# interface_board.net
KiCad netlist of a schematic drawn in EAGLE
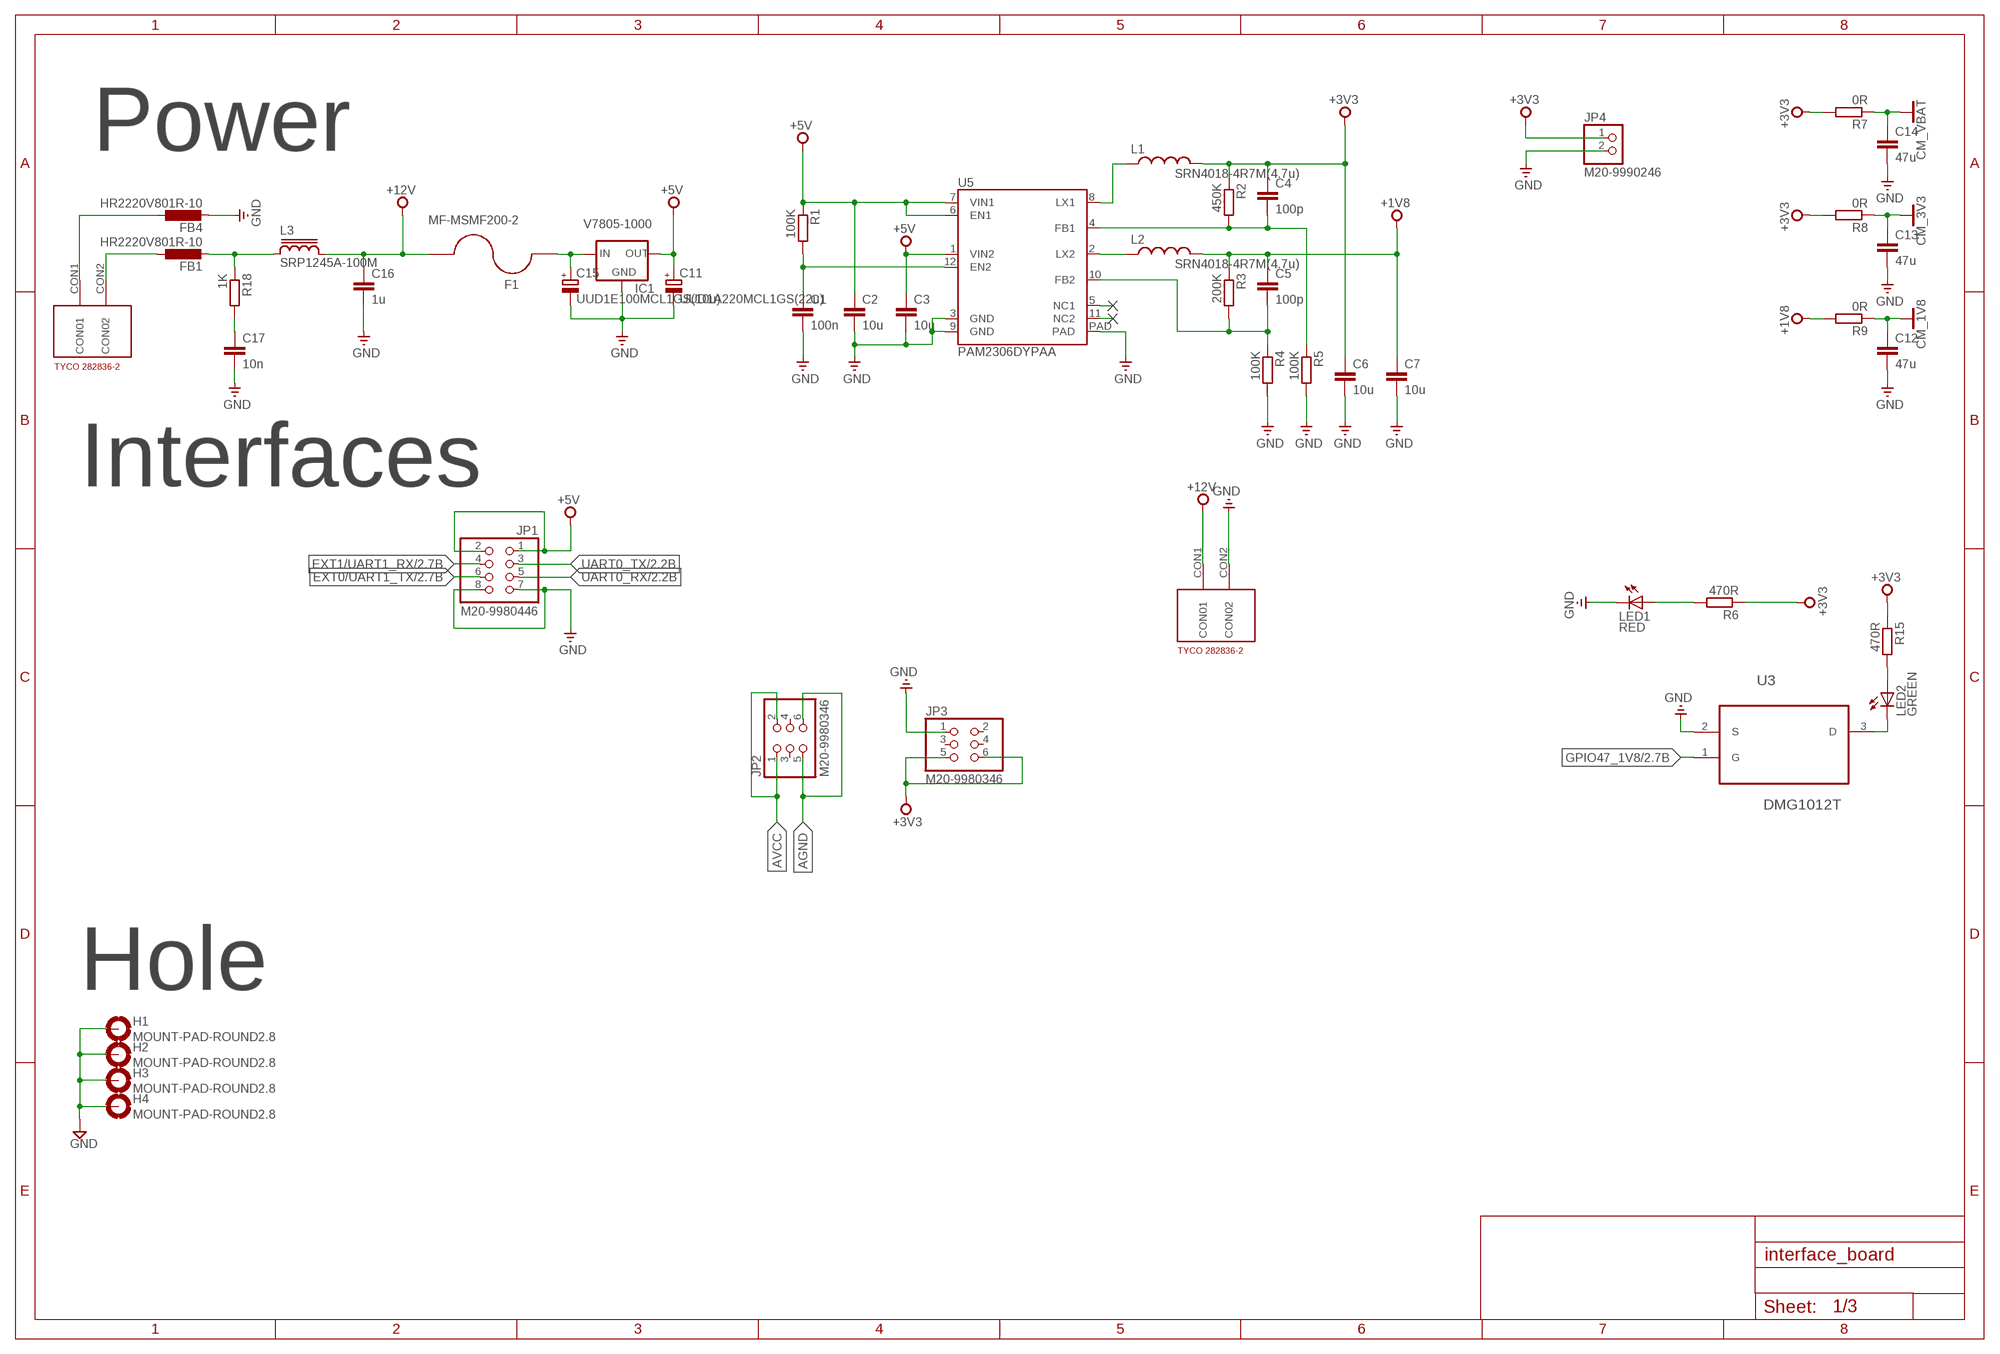
[diagram p0: schematic, sheet 1]
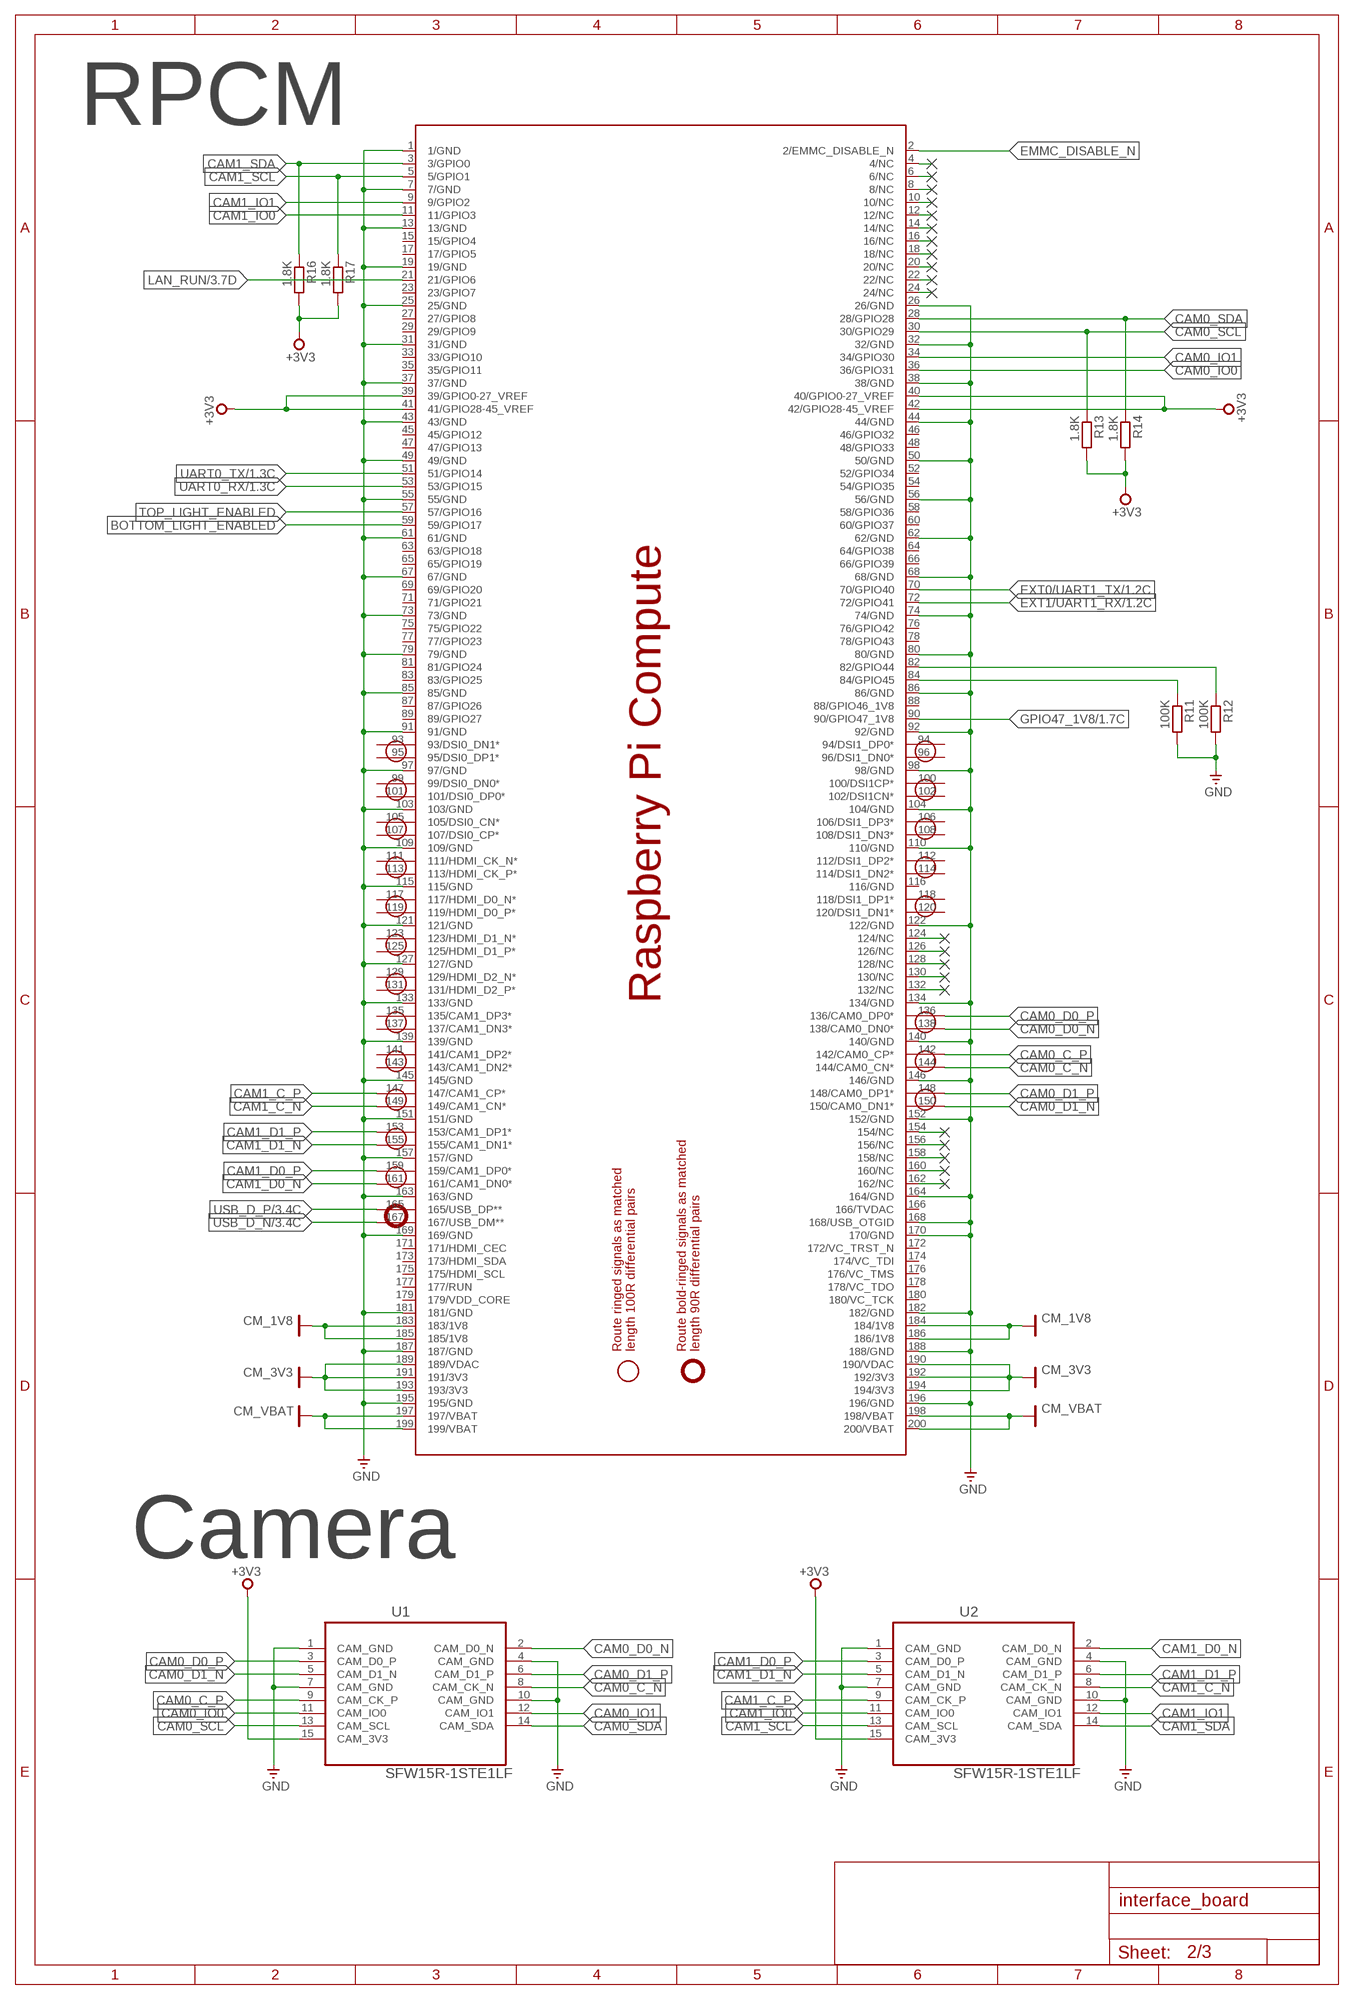
[diagram p1: schematic, sheet 2]
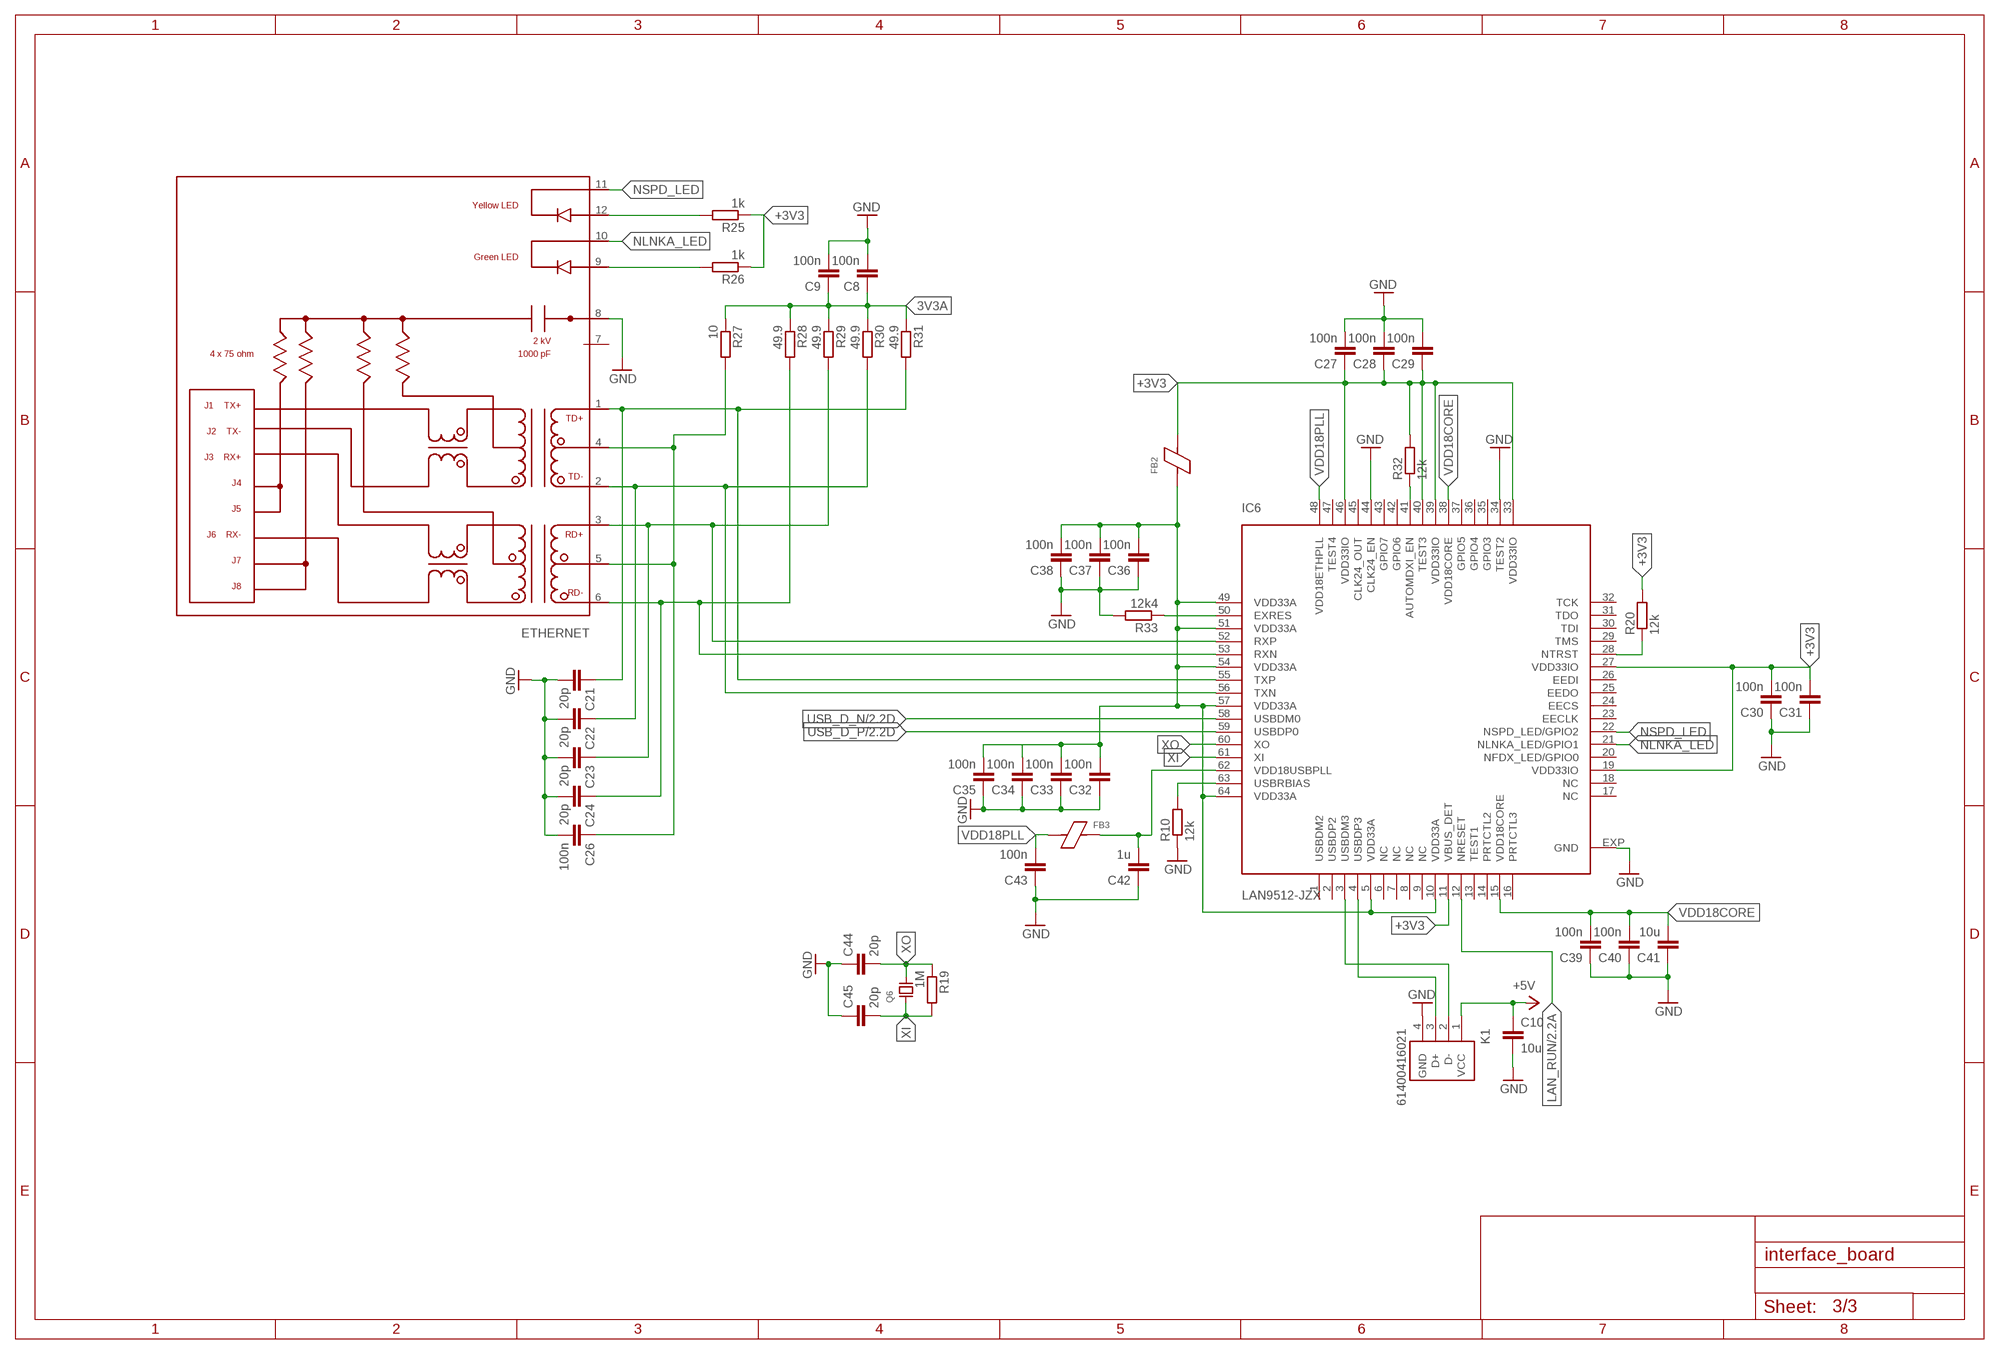
[diagram p2: schematic, sheet 3]

(export (version "E")
  (design (tool "Eeschema 10.0.6"))
  (components
    (comp (ref "C1")
      (value "100n")
      (footprint "eagle-import:C0402")
      (libsource (lib "eagle-import") (part "resistor_C-EUC0402"))
    )
    (comp (ref "C2")
      (value "10u")
      (footprint "eagle-import:C0805")
      (libsource (lib "eagle-import") (part "resistor_C-EUC0805"))
    )
    (comp (ref "C3")
      (value "10u")
      (footprint "eagle-import:C0805")
      (libsource (lib "eagle-import") (part "resistor_C-EUC0805"))
    )
    (comp (ref "C4")
      (value "100p")
      (footprint "eagle-import:C0402")
      (libsource (lib "eagle-import") (part "resistor_C-EUC0402"))
    )
    (comp (ref "C5")
      (value "100p")
      (footprint "eagle-import:C0402")
      (libsource (lib "eagle-import") (part "resistor_C-EUC0402"))
    )
    (comp (ref "C6")
      (value "10u")
      (footprint "eagle-import:C0805")
      (libsource (lib "eagle-import") (part "resistor_C-EUC0805"))
    )
    (comp (ref "C7")
      (value "10u")
      (footprint "eagle-import:C0805")
      (libsource (lib "eagle-import") (part "resistor_C-EUC0805"))
    )
    (comp (ref "C11")
      (value "UUD1A220MCL1GS(22u)")
      (footprint "eagle-import:153CLV-0405")
      (libsource (lib "eagle-import") (part "CPOL-EU153CLV-0405"))
    )
    (comp (ref "C12")
      (value "47u")
      (footprint "eagle-import:C1206")
      (libsource (lib "eagle-import") (part "resistor_C-EUC1206"))
    )
    (comp (ref "C13")
      (value "47u")
      (footprint "eagle-import:C1206")
      (libsource (lib "eagle-import") (part "resistor_C-EUC1206"))
    )
    (comp (ref "C14")
      (value "47u")
      (footprint "eagle-import:C1206")
      (libsource (lib "eagle-import") (part "resistor_C-EUC1206"))
    )
    (comp (ref "C15")
      (value "UUD1E100MCL1GS(10u)")
      (footprint "eagle-import:153CLV-0405")
      (libsource (lib "eagle-import") (part "CPOL-EU153CLV-0405"))
    )
    (comp (ref "C16")
      (value "1u")
      (footprint "eagle-import:C0402")
      (libsource (lib "eagle-import") (part "resistor_C-EUC0402"))
    )
    (comp (ref "C17")
      (value "10n")
      (footprint "eagle-import:C0402")
      (libsource (lib "eagle-import") (part "resistor_C-EUC0402"))
    )
    (comp (ref "F1")
      (value "MF-MSMF200-2")
      (footprint "eagle-import:1812")
      (fields (field (name "MANUFACTURER") "Bourns Inc.") (field (name "PART_NUMBER") "MF-MSMF075/24-2"))
      (libsource (lib "eagle-import") (part "MF-MSMF?075/24"))
    )
    (comp (ref "FB1")
      (value "HR2220V801R-10")
      (footprint "eagle-import:L5650M")
      (libsource (lib "eagle-import") (part "L-EUL5650M"))
    )
    (comp (ref "FB4")
      (value "HR2220V801R-10")
      (footprint "eagle-import:L5650M")
      (libsource (lib "eagle-import") (part "L-EUL5650M"))
    )
    (comp (ref "H1")
      (value "MOUNT-PAD-ROUND2.8")
      (footprint "eagle-import:2,8-PAD")
      (libsource (lib "eagle-import") (part "MOUNT-PAD-ROUND2.8"))
    )
    (comp (ref "H2")
      (value "MOUNT-PAD-ROUND2.8")
      (footprint "eagle-import:2,8-PAD")
      (libsource (lib "eagle-import") (part "MOUNT-PAD-ROUND2.8"))
    )
    (comp (ref "H3")
      (value "MOUNT-PAD-ROUND2.8")
      (footprint "eagle-import:2,8-PAD")
      (libsource (lib "eagle-import") (part "MOUNT-PAD-ROUND2.8"))
    )
    (comp (ref "H4")
      (value "MOUNT-PAD-ROUND2.8")
      (footprint "eagle-import:2,8-PAD")
      (libsource (lib "eagle-import") (part "MOUNT-PAD-ROUND2.8"))
    )
    (comp (ref "IC1")
      (value "V7805-1000")
      (footprint "eagle-import:DIP_3PIN")
      (libsource (lib "eagle-import") (part "VR_1OUTXX"))
    )
    (comp (ref "JP1")
      (value "M20-9980446")
      (footprint "eagle-import:2X04")
      (libsource (lib "eagle-import") (part "PINHD-2X4"))
    )
    (comp (ref "JP2")
      (value "M20-9980346")
      (footprint "eagle-import:2X03")
      (libsource (lib "eagle-import") (part "PINHD-2X3"))
    )
    (comp (ref "JP3")
      (value "M20-9980346")
      (footprint "eagle-import:2X03")
      (libsource (lib "eagle-import") (part "PINHD-2X3"))
    )
    (comp (ref "JP4")
      (value "M20-9990246")
      (footprint "eagle-import:1X02")
      (libsource (lib "eagle-import") (part "PINHD-1X2"))
    )
    (comp (ref "L1")
      (value "SRN4018-4R7M(4.7u)")
      (footprint "eagle-import:BOURNS-SRN4018")
      (libsource (lib "eagle-import") (part "BOURNS-SRN4018"))
    )
    (comp (ref "L2")
      (value "SRN4018-4R7M(4.7u)")
      (footprint "eagle-import:BOURNS-SRN4018")
      (libsource (lib "eagle-import") (part "BOURNS-SRN4018"))
    )
    (comp (ref "L3")
      (value "SRP1245A-100M")
      (footprint "eagle-import:SRP1250A")
      (libsource (lib "eagle-import") (part "SRP1250A"))
    )
    (comp (ref "LED1")
      (value "RED")
      (footprint "eagle-import:CHIP-LED0603")
      (libsource (lib "eagle-import") (part "LEDCHIP-LED0603"))
    )
    (comp (ref "LED2")
      (value "GREEN")
      (footprint "eagle-import:CHIP-LED0603")
      (libsource (lib "eagle-import") (part "LEDCHIP-LED0603"))
    )
    (comp (ref "R1")
      (value "100K")
      (footprint "eagle-import:R0402")
      (libsource (lib "eagle-import") (part "resistor_R-EU_R0402"))
    )
    (comp (ref "R2")
      (value "450K")
      (footprint "eagle-import:R0402")
      (libsource (lib "eagle-import") (part "resistor_R-EU_R0402"))
    )
    (comp (ref "R3")
      (value "200K")
      (footprint "eagle-import:R0402")
      (libsource (lib "eagle-import") (part "resistor_R-EU_R0402"))
    )
    (comp (ref "R4")
      (value "100K")
      (footprint "eagle-import:R0402")
      (libsource (lib "eagle-import") (part "resistor_R-EU_R0402"))
    )
    (comp (ref "R5")
      (value "100K")
      (footprint "eagle-import:R0402")
      (libsource (lib "eagle-import") (part "resistor_R-EU_R0402"))
    )
    (comp (ref "R6")
      (value "470R")
      (footprint "eagle-import:R0402")
      (libsource (lib "eagle-import") (part "resistor_R-EU_R0402"))
    )
    (comp (ref "R7")
      (value "0R")
      (footprint "eagle-import:R0805")
      (libsource (lib "eagle-import") (part "resistor_R-EU_R0805"))
    )
    (comp (ref "R8")
      (value "0R")
      (footprint "eagle-import:R0805")
      (libsource (lib "eagle-import") (part "resistor_R-EU_R0805"))
    )
    (comp (ref "R9")
      (value "0R")
      (footprint "eagle-import:R0805")
      (libsource (lib "eagle-import") (part "resistor_R-EU_R0805"))
    )
    (comp (ref "R15")
      (value "470R")
      (footprint "eagle-import:R0402")
      (libsource (lib "eagle-import") (part "resistor_R-EU_R0402"))
    )
    (comp (ref "R18")
      (value "1K")
      (footprint "eagle-import:R0402")
      (libsource (lib "eagle-import") (part "resistor_R-EU_R0402"))
    )
    (comp (ref "U$1")
      (value "282836-2")
      (footprint "eagle-import:282836-2")
      (libsource (lib "eagle-import") (part "282836-2"))
    )
    (comp (ref "U$2")
      (value "M20-9980346")
      (footprint "eagle-import:282836-2")
      (libsource (lib "eagle-import") (part "282836-2"))
    )
    (comp (ref "U3")
      (value "DMG1012T")
      (footprint "eagle-import:SOT523")
      (libsource (lib "eagle-import") (part "DMG1012T"))
    )
    (comp (ref "U5")
      (value "PAM2306DYPAA")
      (footprint "eagle-import:WDFN3X3-12L")
      (libsource (lib "eagle-import") (part "PAM2306"))
    )
    (comp (ref "PCB1")
      (value "1473005-4")
      (footprint "eagle-import:RPI_COMPUTE")
      (libsource (lib "eagle-import") (part "RPI_COMPUTE"))
    )
    (comp (ref "R11")
      (value "100K")
      (footprint "eagle-import:R0402")
      (libsource (lib "eagle-import") (part "resistor_R-EU_R0402"))
    )
    (comp (ref "R12")
      (value "100K")
      (footprint "eagle-import:R0402")
      (libsource (lib "eagle-import") (part "resistor_R-EU_R0402"))
    )
    (comp (ref "R13")
      (value "1.8K")
      (footprint "eagle-import:R0402")
      (libsource (lib "eagle-import") (part "resistor_R-EU_R0402"))
    )
    (comp (ref "R14")
      (value "1.8K")
      (footprint "eagle-import:R0402")
      (libsource (lib "eagle-import") (part "resistor_R-EU_R0402"))
    )
    (comp (ref "R16")
      (value "1.8K")
      (footprint "eagle-import:R0402")
      (libsource (lib "eagle-import") (part "resistor_R-EU_R0402"))
    )
    (comp (ref "R17")
      (value "1.8K")
      (footprint "eagle-import:R0402")
      (libsource (lib "eagle-import") (part "resistor_R-EU_R0402"))
    )
    (comp (ref "U1")
      (value "SFW15R-1STE1LF")
      (footprint "eagle-import:RPI_CAMERA")
      (fields (field (name "MPN") "SFW16R-1STE1LF"))
      (libsource (lib "eagle-import") (part "RPI_CAMERA"))
    )
    (comp (ref "U2")
      (value "SFW15R-1STE1LF")
      (footprint "eagle-import:RPI_CAMERA")
      (fields (field (name "MPN") "SFW16R-1STE1LF"))
      (libsource (lib "eagle-import") (part "RPI_CAMERA"))
    )
    (comp (ref "C8")
      (value "100n")
      (footprint "eagle-import:C0603")
      (libsource (lib "eagle-import") (part "C-EUC0603"))
    )
    (comp (ref "C9")
      (value "100n")
      (footprint "eagle-import:C0603")
      (libsource (lib "eagle-import") (part "C-EUC0603"))
    )
    (comp (ref "C10")
      (value "10u")
      (footprint "eagle-import:C0805")
      (libsource (lib "eagle-import") (part "C-EUC0805"))
    )
    (comp (ref "C21")
      (value "20p")
      (footprint "eagle-import:C0603")
      (libsource (lib "eagle-import") (part "C-EUC0603"))
    )
    (comp (ref "C22")
      (value "20p")
      (footprint "eagle-import:C0603")
      (libsource (lib "eagle-import") (part "C-EUC0603"))
    )
    (comp (ref "C23")
      (value "20p")
      (footprint "eagle-import:C0603")
      (libsource (lib "eagle-import") (part "C-EUC0603"))
    )
    (comp (ref "C24")
      (value "20p")
      (footprint "eagle-import:C0603")
      (libsource (lib "eagle-import") (part "C-EUC0603"))
    )
    (comp (ref "C26")
      (value "100n")
      (footprint "eagle-import:C0603")
      (libsource (lib "eagle-import") (part "C-EUC0603"))
    )
    (comp (ref "C27")
      (value "100n")
      (footprint "eagle-import:C0603")
      (libsource (lib "eagle-import") (part "C-EUC0603"))
    )
    (comp (ref "C28")
      (value "100n")
      (footprint "eagle-import:C0603")
      (libsource (lib "eagle-import") (part "C-EUC0603"))
    )
    (comp (ref "C29")
      (value "100n")
      (footprint "eagle-import:C0603")
      (libsource (lib "eagle-import") (part "C-EUC0603"))
    )
    (comp (ref "C30")
      (value "100n")
      (footprint "eagle-import:C0603")
      (libsource (lib "eagle-import") (part "C-EUC0603"))
    )
    (comp (ref "C31")
      (value "100n")
      (footprint "eagle-import:C0603")
      (libsource (lib "eagle-import") (part "C-EUC0603"))
    )
    (comp (ref "C32")
      (value "100n")
      (footprint "eagle-import:C0603")
      (libsource (lib "eagle-import") (part "C-EUC0603"))
    )
    (comp (ref "C33")
      (value "100n")
      (footprint "eagle-import:C0603")
      (libsource (lib "eagle-import") (part "C-EUC0603"))
    )
    (comp (ref "C34")
      (value "100n")
      (footprint "eagle-import:C0603")
      (libsource (lib "eagle-import") (part "C-EUC0603"))
    )
    (comp (ref "C35")
      (value "100n")
      (footprint "eagle-import:C0603")
      (libsource (lib "eagle-import") (part "C-EUC0603"))
    )
    (comp (ref "C36")
      (value "100n")
      (footprint "eagle-import:C0603")
      (libsource (lib "eagle-import") (part "C-EUC0603"))
    )
    (comp (ref "C37")
      (value "100n")
      (footprint "eagle-import:C0603")
      (libsource (lib "eagle-import") (part "C-EUC0603"))
    )
    (comp (ref "C38")
      (value "100n")
      (footprint "eagle-import:C0603")
      (libsource (lib "eagle-import") (part "C-EUC0603"))
    )
    (comp (ref "C39")
      (value "100n")
      (footprint "eagle-import:C0603")
      (libsource (lib "eagle-import") (part "C-EUC0603"))
    )
    (comp (ref "C40")
      (value "100n")
      (footprint "eagle-import:C0603")
      (libsource (lib "eagle-import") (part "C-EUC0603"))
    )
    (comp (ref "C41")
      (value "10u")
      (footprint "eagle-import:C0805")
      (libsource (lib "eagle-import") (part "C-EUC0805"))
    )
    (comp (ref "C42")
      (value "1u")
      (footprint "eagle-import:C0805")
      (libsource (lib "eagle-import") (part "C-EUC0805"))
    )
    (comp (ref "C43")
      (value "100n")
      (footprint "eagle-import:C0603")
      (libsource (lib "eagle-import") (part "C-EUC0603"))
    )
    (comp (ref "C44")
      (value "20p")
      (footprint "eagle-import:C0603")
      (libsource (lib "eagle-import") (part "C-EUC0603"))
    )
    (comp (ref "C45")
      (value "20p")
      (footprint "eagle-import:C0603")
      (libsource (lib "eagle-import") (part "C-EUC0603"))
    )
    (comp (ref "ETHERNET")
      (value "HR911105A")
      (footprint "eagle-import:RJ45")
      (libsource (lib "eagle-import") (part "HR911105A"))
    )
    (comp (ref "FB2")
      (value "742792022")
      (footprint "eagle-import:C0805")
      (libsource (lib "eagle-import") (part "FERRITE_BEAD"))
    )
    (comp (ref "FB3")
      (value "742792022")
      (footprint "eagle-import:C0805")
      (libsource (lib "eagle-import") (part "FERRITE_BEAD"))
    )
    (comp (ref "IC6")
      (value "LAN9512-JZX")
      (footprint "eagle-import:QFN64-9X9")
      (libsource (lib "eagle-import") (part "LAN9512"))
    )
    (comp (ref "K1")
      (value "61400416021")
      (footprint "eagle-import:61400416021")
      (libsource (lib "eagle-import") (part "61400416021"))
    )
    (comp (ref "Q6")
      (value "CTS_32X25_SMD")
      (footprint "eagle-import:CTS_32X25")
      (libsource (lib "eagle-import") (part "CTS_32X25_SMD"))
    )
    (comp (ref "R10")
      (value "12k")
      (footprint "eagle-import:R0603")
      (libsource (lib "eagle-import") (part "R-EU_R0603"))
    )
    (comp (ref "R19")
      (value "1M")
      (footprint "eagle-import:R0603")
      (libsource (lib "eagle-import") (part "R-EU_R0603"))
    )
    (comp (ref "R20")
      (value "12k")
      (footprint "eagle-import:R0603")
      (libsource (lib "eagle-import") (part "R-EU_R0603"))
    )
    (comp (ref "R25")
      (value "1k")
      (footprint "eagle-import:R0603")
      (libsource (lib "eagle-import") (part "R-EU_R0603"))
    )
    (comp (ref "R26")
      (value "1k")
      (footprint "eagle-import:R0603")
      (libsource (lib "eagle-import") (part "R-EU_R0603"))
    )
    (comp (ref "R27")
      (value "10")
      (footprint "eagle-import:R0603")
      (libsource (lib "eagle-import") (part "R-EU_R0603"))
    )
    (comp (ref "R28")
      (value "49.9")
      (footprint "eagle-import:R0603")
      (libsource (lib "eagle-import") (part "R-EU_R0603"))
    )
    (comp (ref "R29")
      (value "49.9")
      (footprint "eagle-import:R0603")
      (libsource (lib "eagle-import") (part "R-EU_R0603"))
    )
    (comp (ref "R30")
      (value "49.9")
      (footprint "eagle-import:R0603")
      (libsource (lib "eagle-import") (part "R-EU_R0603"))
    )
    (comp (ref "R31")
      (value "49.9")
      (footprint "eagle-import:R0603")
      (libsource (lib "eagle-import") (part "R-EU_R0603"))
    )
    (comp (ref "R32")
      (value "12k")
      (footprint "eagle-import:R0603")
      (libsource (lib "eagle-import") (part "R-EU_R0603"))
    )
    (comp (ref "R33")
      (value "12k4")
      (footprint "eagle-import:R0603")
      (libsource (lib "eagle-import") (part "R-EU_R0603"))
    )
  )
  (nets
    (net (code "1") (name "+1V8") (class "Default")
      (node (ref "C5") (pin "1") (pinfunction "1_1") (pintype "passive"))
      (node (ref "C7") (pin "1") (pinfunction "1_1") (pintype "passive"))
      (node (ref "L2") (pin "P$1") (pinfunction "1_P$1") (pintype "passive"))
      (node (ref "R3") (pin "1") (pinfunction "1_1") (pintype "passive"))
      (node (ref "R9") (pin "2") (pinfunction "2_2") (pintype "passive"))
    )
    (net (code "2") (name "+3V3") (class "Default")
      (node (ref "C27") (pin "1") (pinfunction "1_1") (pintype "passive"))
      (node (ref "C28") (pin "1") (pinfunction "1_1") (pintype "passive"))
      (node (ref "C29") (pin "1") (pinfunction "1_1") (pintype "passive"))
      (node (ref "C30") (pin "2") (pinfunction "2_2") (pintype "passive"))
      (node (ref "C31") (pin "2") (pinfunction "2_2") (pintype "passive"))
      (node (ref "C4") (pin "1") (pinfunction "1_1") (pintype "passive"))
      (node (ref "C6") (pin "1") (pinfunction "1_1") (pintype "passive"))
      (node (ref "FB2") (pin "2") (pinfunction "P$2_2") (pintype "bidirectional"))
      (node (ref "IC6") (pin "11") (pinfunction "VBUS_DET_11") (pintype "bidirectional"))
      (node (ref "IC6") (pin "19") (pinfunction "VDD33IO_19") (pintype "bidirectional"))
      (node (ref "IC6") (pin "27") (pinfunction "VDD33IO_27") (pintype "bidirectional"))
      (node (ref "IC6") (pin "33") (pinfunction "VDD33IO_33") (pintype "bidirectional"))
      (node (ref "IC6") (pin "39") (pinfunction "VDD33IO_39") (pintype "bidirectional"))
      (node (ref "IC6") (pin "40") (pinfunction "TEST3_40") (pintype "bidirectional"))
      (node (ref "IC6") (pin "46") (pinfunction "VDD33IO_46") (pintype "bidirectional"))
      (node (ref "JP3") (pin "5") (pinfunction "5_5") (pintype "passive"))
      (node (ref "JP3") (pin "6") (pinfunction "6_6") (pintype "passive"))
      (node (ref "JP4") (pin "1") (pinfunction "1_1") (pintype "passive"))
      (node (ref "L1") (pin "P$1") (pinfunction "1_P$1") (pintype "passive"))
      (node (ref "PCB1") (pin "39") (pinfunction "39/GPIO0-27_VREF_39") (pintype "bidirectional"))
      (node (ref "PCB1") (pin "40") (pinfunction "40/GPIO0-27_VREF_40") (pintype "bidirectional"))
      (node (ref "PCB1") (pin "41") (pinfunction "41/GPIO28-45_VREF_41") (pintype "bidirectional"))
      (node (ref "PCB1") (pin "42") (pinfunction "42/GPIO28-45_VREF_42") (pintype "bidirectional"))
      (node (ref "R13") (pin "2") (pinfunction "2_2") (pintype "passive"))
      (node (ref "R14") (pin "2") (pinfunction "2_2") (pintype "passive"))
      (node (ref "R15") (pin "1") (pinfunction "1_1") (pintype "passive"))
      (node (ref "R16") (pin "2") (pinfunction "2_2") (pintype "passive"))
      (node (ref "R17") (pin "2") (pinfunction "2_2") (pintype "passive"))
      (node (ref "R2") (pin "1") (pinfunction "1_1") (pintype "passive"))
      (node (ref "R20") (pin "2") (pinfunction "2_2") (pintype "passive"))
      (node (ref "R25") (pin "1") (pinfunction "1_1") (pintype "passive"))
      (node (ref "R26") (pin "1") (pinfunction "1_1") (pintype "passive"))
      (node (ref "R32") (pin "2") (pinfunction "2_2") (pintype "passive"))
      (node (ref "R6") (pin "1") (pinfunction "1_1") (pintype "passive"))
      (node (ref "R7") (pin "2") (pinfunction "2_2") (pintype "passive"))
      (node (ref "R8") (pin "2") (pinfunction "2_2") (pintype "passive"))
      (node (ref "U1") (pin "15") (pinfunction "CAM_3V3_15") (pintype "passive"))
      (node (ref "U2") (pin "15") (pinfunction "CAM_3V3_15") (pintype "passive"))
    )
    (net (code "3") (name "+5V") (class "Default")
      (node (ref "C10") (pin "1") (pinfunction "1_1") (pintype "passive"))
      (node (ref "C11") (pin "+") (pinfunction "+_+") (pintype "passive"))
      (node (ref "C2") (pin "1") (pinfunction "1_1") (pintype "passive"))
      (node (ref "C3") (pin "1") (pinfunction "1_1") (pintype "passive"))
      (node (ref "IC1") (pin "OUT") (pinfunction "OUT_OUT") (pintype "passive"))
      (node (ref "JP1") (pin "1") (pinfunction "1_1") (pintype "passive"))
      (node (ref "JP1") (pin "2") (pinfunction "2_2") (pintype "passive"))
      (node (ref "K1") (pin "1") (pinfunction "VCC_1") (pintype "passive"))
      (node (ref "R1") (pin "1") (pinfunction "1_1") (pintype "passive"))
      (node (ref "U5") (pin "1") (pinfunction "VIN2_1") (pintype "bidirectional"))
      (node (ref "U5") (pin "6") (pinfunction "EN1_6") (pintype "bidirectional"))
      (node (ref "U5") (pin "7") (pinfunction "VIN1_7") (pintype "bidirectional"))
    )
    (net (code "4") (name "+12V") (class "Default")
      (node (ref "C16") (pin "1") (pinfunction "1_1") (pintype "passive"))
      (node (ref "F1") (pin "1") (pinfunction "1_1") (pintype "passive"))
      (node (ref "L3") (pin "2") (pinfunction "2_2") (pintype "passive"))
      (node (ref "U$2") (pin "CON1") (pinfunction "CON01_CON1") (pintype "bidirectional"))
    )
    (net (code "5") (name "3V3A") (class "Default")
      (node (ref "C8") (pin "1") (pinfunction "1_1") (pintype "passive"))
      (node (ref "C9") (pin "1") (pinfunction "1_1") (pintype "passive"))
      (node (ref "R27") (pin "1") (pinfunction "1_1") (pintype "passive"))
      (node (ref "R28") (pin "1") (pinfunction "1_1") (pintype "passive"))
      (node (ref "R29") (pin "1") (pinfunction "1_1") (pintype "passive"))
      (node (ref "R30") (pin "1") (pinfunction "1_1") (pintype "passive"))
      (node (ref "R31") (pin "1") (pinfunction "1_1") (pintype "passive"))
    )
    (net (code "6") (name "AGND") (class "Default")
      (node (ref "FB4") (pin "1") (pinfunction "1_1") (pintype "passive"))
      (node (ref "JP2") (pin "5") (pinfunction "5_5") (pintype "passive"))
      (node (ref "JP2") (pin "6") (pinfunction "6_6") (pintype "passive"))
      (node (ref "U$1") (pin "CON1") (pinfunction "CON01_CON1") (pintype "bidirectional"))
    )
    (net (code "7") (name "AVCC") (class "Default")
      (node (ref "FB1") (pin "1") (pinfunction "1_1") (pintype "passive"))
      (node (ref "JP2") (pin "1") (pinfunction "1_1") (pintype "passive"))
      (node (ref "JP2") (pin "2") (pinfunction "2_2") (pintype "passive"))
      (node (ref "U$1") (pin "CON2") (pinfunction "CON02_CON2") (pintype "bidirectional"))
    )
    (net (code "8") (name "BOTTOM_LIGHT_ENABLED") (class "Default")
      (node (ref "PCB1") (pin "59") (pinfunction "59/GPIO17_59") (pintype "bidirectional"))
    )
    (net (code "9") (name "CAM0_C_N") (class "Default")
      (node (ref "PCB1") (pin "144") (pinfunction "144/CAM0_CN*_144") (pintype "bidirectional"))
      (node (ref "U1") (pin "8") (pinfunction "CAM_CK_N_8") (pintype "passive"))
    )
    (net (code "10") (name "CAM0_C_P") (class "Default")
      (node (ref "PCB1") (pin "142") (pinfunction "142/CAM0_CP*_142") (pintype "bidirectional"))
      (node (ref "U1") (pin "9") (pinfunction "CAM_CK_P_9") (pintype "passive"))
    )
    (net (code "11") (name "CAM0_D0_N") (class "Default")
      (node (ref "PCB1") (pin "138") (pinfunction "138/CAM0_DN0*_138") (pintype "bidirectional"))
      (node (ref "U1") (pin "2") (pinfunction "CAM_D0_N_2") (pintype "passive"))
    )
    (net (code "12") (name "CAM0_D0_P") (class "Default")
      (node (ref "PCB1") (pin "136") (pinfunction "136/CAM0_DP0*_136") (pintype "bidirectional"))
      (node (ref "U1") (pin "3") (pinfunction "CAM_D0_P_3") (pintype "passive"))
    )
    (net (code "13") (name "CAM0_D1_N") (class "Default")
      (node (ref "PCB1") (pin "150") (pinfunction "150/CAM0_DN1*_150") (pintype "bidirectional"))
      (node (ref "U1") (pin "5") (pinfunction "CAM_D1_N_5") (pintype "passive"))
    )
    (net (code "14") (name "CAM0_D1_P") (class "Default")
      (node (ref "PCB1") (pin "148") (pinfunction "148/CAM0_DP1*_148") (pintype "bidirectional"))
      (node (ref "U1") (pin "6") (pinfunction "CAM_D1_P_6") (pintype "passive"))
    )
    (net (code "15") (name "CAM0_IO0") (class "Default")
      (node (ref "PCB1") (pin "36") (pinfunction "36/GPIO31_36") (pintype "bidirectional"))
      (node (ref "U1") (pin "11") (pinfunction "CAM_IO0_11") (pintype "passive"))
    )
    (net (code "16") (name "CAM0_IO1") (class "Default")
      (node (ref "PCB1") (pin "34") (pinfunction "34/GPIO30_34") (pintype "bidirectional"))
      (node (ref "U1") (pin "12") (pinfunction "CAM_IO1_12") (pintype "passive"))
    )
    (net (code "17") (name "CAM0_SCL") (class "Default")
      (node (ref "PCB1") (pin "30") (pinfunction "30/GPIO29_30") (pintype "bidirectional"))
      (node (ref "R13") (pin "1") (pinfunction "1_1") (pintype "passive"))
      (node (ref "U1") (pin "13") (pinfunction "CAM_SCL_13") (pintype "passive"))
    )
    (net (code "18") (name "CAM0_SDA") (class "Default")
      (node (ref "PCB1") (pin "28") (pinfunction "28/GPIO28_28") (pintype "bidirectional"))
      (node (ref "R14") (pin "1") (pinfunction "1_1") (pintype "passive"))
      (node (ref "U1") (pin "14") (pinfunction "CAM_SDA_14") (pintype "passive"))
    )
    (net (code "19") (name "CAM1_C_N") (class "Default")
      (node (ref "PCB1") (pin "149") (pinfunction "149/CAM1_CN*_149") (pintype "bidirectional"))
      (node (ref "U2") (pin "8") (pinfunction "CAM_CK_N_8") (pintype "passive"))
    )
    (net (code "20") (name "CAM1_C_P") (class "Default")
      (node (ref "PCB1") (pin "147") (pinfunction "147/CAM1_CP*_147") (pintype "bidirectional"))
      (node (ref "U2") (pin "9") (pinfunction "CAM_CK_P_9") (pintype "passive"))
    )
    (net (code "21") (name "CAM1_D0_N") (class "Default")
      (node (ref "PCB1") (pin "161") (pinfunction "161/CAM1_DN0*_161") (pintype "bidirectional"))
      (node (ref "U2") (pin "2") (pinfunction "CAM_D0_N_2") (pintype "passive"))
    )
    (net (code "22") (name "CAM1_D0_P") (class "Default")
      (node (ref "PCB1") (pin "159") (pinfunction "159/CAM1_DP0*_159") (pintype "bidirectional"))
      (node (ref "U2") (pin "3") (pinfunction "CAM_D0_P_3") (pintype "passive"))
    )
    (net (code "23") (name "CAM1_D1_N") (class "Default")
      (node (ref "PCB1") (pin "155") (pinfunction "155/CAM1_DN1*_155") (pintype "bidirectional"))
      (node (ref "U2") (pin "5") (pinfunction "CAM_D1_N_5") (pintype "passive"))
    )
    (net (code "24") (name "CAM1_D1_P") (class "Default")
      (node (ref "PCB1") (pin "153") (pinfunction "153/CAM1_DP1*_153") (pintype "bidirectional"))
      (node (ref "U2") (pin "6") (pinfunction "CAM_D1_P_6") (pintype "passive"))
    )
    (net (code "25") (name "CAM1_IO0") (class "Default")
      (node (ref "PCB1") (pin "11") (pinfunction "11/GPIO3_11") (pintype "bidirectional"))
      (node (ref "U2") (pin "11") (pinfunction "CAM_IO0_11") (pintype "passive"))
    )
    (net (code "26") (name "CAM1_IO1") (class "Default")
      (node (ref "PCB1") (pin "9") (pinfunction "9/GPIO2_9") (pintype "bidirectional"))
      (node (ref "U2") (pin "12") (pinfunction "CAM_IO1_12") (pintype "passive"))
    )
    (net (code "27") (name "CAM1_SCL") (class "Default")
      (node (ref "PCB1") (pin "5") (pinfunction "5/GPIO1_5") (pintype "bidirectional"))
      (node (ref "R17") (pin "1") (pinfunction "1_1") (pintype "passive"))
      (node (ref "U2") (pin "13") (pinfunction "CAM_SCL_13") (pintype "passive"))
    )
    (net (code "28") (name "CAM1_SDA") (class "Default")
      (node (ref "PCB1") (pin "3") (pinfunction "3/GPIO0_3") (pintype "bidirectional"))
      (node (ref "R16") (pin "1") (pinfunction "1_1") (pintype "passive"))
      (node (ref "U2") (pin "14") (pinfunction "CAM_SDA_14") (pintype "passive"))
    )
    (net (code "29") (name "CM_1V8") (class "Default")
      (node (ref "C12") (pin "1") (pinfunction "1_1") (pintype "passive"))
      (node (ref "PCB1") (pin "183") (pinfunction "183/1V8_183") (pintype "bidirectional"))
      (node (ref "PCB1") (pin "184") (pinfunction "184/1V8_184") (pintype "bidirectional"))
      (node (ref "PCB1") (pin "185") (pinfunction "185/1V8_185") (pintype "bidirectional"))
      (node (ref "PCB1") (pin "186") (pinfunction "186/1V8_186") (pintype "bidirectional"))
      (node (ref "R9") (pin "1") (pinfunction "1_1") (pintype "passive"))
    )
    (net (code "30") (name "CM_3V3") (class "Default")
      (node (ref "C13") (pin "1") (pinfunction "1_1") (pintype "passive"))
      (node (ref "PCB1") (pin "189") (pinfunction "189/VDAC_189") (pintype "bidirectional"))
      (node (ref "PCB1") (pin "190") (pinfunction "190/VDAC_190") (pintype "bidirectional"))
      (node (ref "PCB1") (pin "191") (pinfunction "191/3V3_191") (pintype "bidirectional"))
      (node (ref "PCB1") (pin "192") (pinfunction "192/3V3_192") (pintype "bidirectional"))
      (node (ref "PCB1") (pin "193") (pinfunction "193/3V3_193") (pintype "bidirectional"))
      (node (ref "PCB1") (pin "194") (pinfunction "194/3V3_194") (pintype "bidirectional"))
      (node (ref "R8") (pin "1") (pinfunction "1_1") (pintype "passive"))
    )
    (net (code "31") (name "CM_VBAT") (class "Default")
      (node (ref "C14") (pin "1") (pinfunction "1_1") (pintype "passive"))
      (node (ref "PCB1") (pin "197") (pinfunction "197/VBAT_197") (pintype "bidirectional"))
      (node (ref "PCB1") (pin "198") (pinfunction "198/VBAT_198") (pintype "bidirectional"))
      (node (ref "PCB1") (pin "199") (pinfunction "199/VBAT_199") (pintype "bidirectional"))
      (node (ref "PCB1") (pin "200") (pinfunction "200/VBAT_200") (pintype "bidirectional"))
      (node (ref "R7") (pin "1") (pinfunction "1_1") (pintype "passive"))
    )
    (net (code "32") (name "EMMC_DISABLE_N") (class "Default")
      (node (ref "PCB1") (pin "2") (pinfunction "2/EMMC_DISABLE_N_2") (pintype "bidirectional"))
    )
    (net (code "33") (name "EXT0{slash}UART1_TX") (class "Default")
      (node (ref "JP1") (pin "6") (pinfunction "6_6") (pintype "passive"))
      (node (ref "PCB1") (pin "70") (pinfunction "70/GPIO40_70") (pintype "bidirectional"))
    )
    (net (code "34") (name "EXT1{slash}UART1_RX") (class "Default")
      (node (ref "JP1") (pin "4") (pinfunction "4_4") (pintype "passive"))
      (node (ref "PCB1") (pin "72") (pinfunction "72/GPIO41_72") (pintype "bidirectional"))
    )
    (net (code "35") (name "GND") (class "Default")
      (node (ref "C1") (pin "2") (pinfunction "2_2") (pintype "passive"))
      (node (ref "C10") (pin "2") (pinfunction "2_2") (pintype "passive"))
      (node (ref "C11") (pin "-") (pinfunction "-_-") (pintype "passive"))
      (node (ref "C12") (pin "2") (pinfunction "2_2") (pintype "passive"))
      (node (ref "C13") (pin "2") (pinfunction "2_2") (pintype "passive"))
      (node (ref "C14") (pin "2") (pinfunction "2_2") (pintype "passive"))
      (node (ref "C15") (pin "-") (pinfunction "-_-") (pintype "passive"))
      (node (ref "C16") (pin "2") (pinfunction "2_2") (pintype "passive"))
      (node (ref "C17") (pin "2") (pinfunction "2_2") (pintype "passive"))
      (node (ref "C2") (pin "2") (pinfunction "2_2") (pintype "passive"))
      (node (ref "C21") (pin "2") (pinfunction "2_2") (pintype "passive"))
      (node (ref "C22") (pin "2") (pinfunction "2_2") (pintype "passive"))
      (node (ref "C23") (pin "2") (pinfunction "2_2") (pintype "passive"))
      (node (ref "C24") (pin "2") (pinfunction "2_2") (pintype "passive"))
      (node (ref "C26") (pin "2") (pinfunction "2_2") (pintype "passive"))
      (node (ref "C27") (pin "2") (pinfunction "2_2") (pintype "passive"))
      (node (ref "C28") (pin "2") (pinfunction "2_2") (pintype "passive"))
      (node (ref "C29") (pin "2") (pinfunction "2_2") (pintype "passive"))
      (node (ref "C3") (pin "2") (pinfunction "2_2") (pintype "passive"))
      (node (ref "C30") (pin "1") (pinfunction "1_1") (pintype "passive"))
      (node (ref "C31") (pin "1") (pinfunction "1_1") (pintype "passive"))
      (node (ref "C32") (pin "1") (pinfunction "1_1") (pintype "passive"))
      (node (ref "C33") (pin "1") (pinfunction "1_1") (pintype "passive"))
      (node (ref "C34") (pin "1") (pinfunction "1_1") (pintype "passive"))
      (node (ref "C35") (pin "1") (pinfunction "1_1") (pintype "passive"))
      (node (ref "C36") (pin "1") (pinfunction "1_1") (pintype "passive"))
      (node (ref "C37") (pin "1") (pinfunction "1_1") (pintype "passive"))
      (node (ref "C38") (pin "1") (pinfunction "1_1") (pintype "passive"))
      (node (ref "C39") (pin "1") (pinfunction "1_1") (pintype "passive"))
      (node (ref "C40") (pin "1") (pinfunction "1_1") (pintype "passive"))
      (node (ref "C41") (pin "1") (pinfunction "1_1") (pintype "passive"))
      (node (ref "C42") (pin "1") (pinfunction "1_1") (pintype "passive"))
      (node (ref "C43") (pin "1") (pinfunction "1_1") (pintype "passive"))
      (node (ref "C44") (pin "1") (pinfunction "1_1") (pintype "passive"))
      (node (ref "C45") (pin "1") (pinfunction "1_1") (pintype "passive"))
      (node (ref "C6") (pin "2") (pinfunction "2_2") (pintype "passive"))
      (node (ref "C7") (pin "2") (pinfunction "2_2") (pintype "passive"))
      (node (ref "C8") (pin "2") (pinfunction "2_2") (pintype "passive"))
      (node (ref "C9") (pin "2") (pinfunction "2_2") (pintype "passive"))
      (node (ref "ETHERNET") (pin "8") (pinfunction "P$8_8") (pintype "bidirectional"))
      (node (ref "FB4") (pin "2") (pinfunction "2_2") (pintype "passive"))
      (node (ref "H1") (pin "B2,8") (pinfunction "MOUNT_B2,8") (pintype "passive"))
      (node (ref "H2") (pin "B2,8") (pinfunction "MOUNT_B2,8") (pintype "passive"))
      (node (ref "H3") (pin "B2,8") (pinfunction "MOUNT_B2,8") (pintype "passive"))
      (node (ref "H4") (pin "B2,8") (pinfunction "MOUNT_B2,8") (pintype "passive"))
      (node (ref "IC1") (pin "GND") (pinfunction "GND_GND") (pintype "input"))
      (node (ref "IC6") (pin "34") (pinfunction "TEST2_34") (pintype "bidirectional"))
      (node (ref "IC6") (pin "44") (pinfunction "CLK24_EN_44") (pintype "bidirectional"))
      (node (ref "IC6") (pin "EXP") (pinfunction "GND_EXP") (pintype "bidirectional"))
      (node (ref "JP1") (pin "7") (pinfunction "7_7") (pintype "passive"))
      (node (ref "JP1") (pin "8") (pinfunction "8_8") (pintype "passive"))
      (node (ref "JP3") (pin "1") (pinfunction "1_1") (pintype "passive"))
      (node (ref "JP4") (pin "2") (pinfunction "2_2") (pintype "passive"))
      (node (ref "K1") (pin "4") (pinfunction "GND_4") (pintype "passive"))
      (node (ref "LED1") (pin "C") (pinfunction "C_C") (pintype "passive"))
      (node (ref "PCB1") (pin "1") (pinfunction "1/GND_1") (pintype "bidirectional"))
      (node (ref "PCB1") (pin "103") (pinfunction "103/GND_103") (pintype "bidirectional"))
      (node (ref "PCB1") (pin "104") (pinfunction "104/GND_104") (pintype "bidirectional"))
      (node (ref "PCB1") (pin "109") (pinfunction "109/GND_109") (pintype "bidirectional"))
      (node (ref "PCB1") (pin "110") (pinfunction "110/GND_110") (pintype "bidirectional"))
      (node (ref "PCB1") (pin "115") (pinfunction "115/GND_115") (pintype "bidirectional"))
      (node (ref "PCB1") (pin "121") (pinfunction "121/GND_121") (pintype "bidirectional"))
      (node (ref "PCB1") (pin "122") (pinfunction "122/GND_122") (pintype "bidirectional"))
      (node (ref "PCB1") (pin "127") (pinfunction "127/GND_127") (pintype "bidirectional"))
      (node (ref "PCB1") (pin "13") (pinfunction "13/GND_13") (pintype "bidirectional"))
      (node (ref "PCB1") (pin "133") (pinfunction "133/GND_133") (pintype "bidirectional"))
      (node (ref "PCB1") (pin "134") (pinfunction "134/GND_134") (pintype "bidirectional"))
      (node (ref "PCB1") (pin "139") (pinfunction "139/GND_139") (pintype "bidirectional"))
      (node (ref "PCB1") (pin "140") (pinfunction "140/GND_140") (pintype "bidirectional"))
      (node (ref "PCB1") (pin "145") (pinfunction "145/GND_145") (pintype "bidirectional"))
      (node (ref "PCB1") (pin "146") (pinfunction "146/GND_146") (pintype "bidirectional"))
      (node (ref "PCB1") (pin "151") (pinfunction "151/GND_151") (pintype "bidirectional"))
      (node (ref "PCB1") (pin "152") (pinfunction "152/GND_152") (pintype "bidirectional"))
      (node (ref "PCB1") (pin "157") (pinfunction "157/GND_157") (pintype "bidirectional"))
      (node (ref "PCB1") (pin "163") (pinfunction "163/GND_163") (pintype "bidirectional"))
      (node (ref "PCB1") (pin "164") (pinfunction "164/GND_164") (pintype "bidirectional"))
      (node (ref "PCB1") (pin "168") (pinfunction "168/USB_OTGID_168") (pintype "bidirectional"))
      (node (ref "PCB1") (pin "169") (pinfunction "169/GND_169") (pintype "bidirectional"))
      (node (ref "PCB1") (pin "170") (pinfunction "170/GND_170") (pintype "bidirectional"))
      (node (ref "PCB1") (pin "181") (pinfunction "181/GND_181") (pintype "bidirectional"))
      (node (ref "PCB1") (pin "182") (pinfunction "182/GND_182") (pintype "bidirectional"))
      (node (ref "PCB1") (pin "187") (pinfunction "187/GND_187") (pintype "bidirectional"))
      (node (ref "PCB1") (pin "188") (pinfunction "188/GND_188") (pintype "bidirectional"))
      (node (ref "PCB1") (pin "19") (pinfunction "19/GND_19") (pintype "bidirectional"))
      (node (ref "PCB1") (pin "195") (pinfunction "195/GND_195") (pintype "bidirectional"))
      (node (ref "PCB1") (pin "196") (pinfunction "196/GND_196") (pintype "bidirectional"))
      (node (ref "PCB1") (pin "25") (pinfunction "25/GND_25") (pintype "bidirectional"))
      (node (ref "PCB1") (pin "26") (pinfunction "26/GND_26") (pintype "bidirectional"))
      (node (ref "PCB1") (pin "31") (pinfunction "31/GND_31") (pintype "bidirectional"))
      (node (ref "PCB1") (pin "32") (pinfunction "32/GND_32") (pintype "bidirectional"))
      (node (ref "PCB1") (pin "37") (pinfunction "37/GND_37") (pintype "bidirectional"))
      (node (ref "PCB1") (pin "38") (pinfunction "38/GND_38") (pintype "bidirectional"))
      (node (ref "PCB1") (pin "43") (pinfunction "43/GND_43") (pintype "bidirectional"))
      (node (ref "PCB1") (pin "44") (pinfunction "44/GND_44") (pintype "bidirectional"))
      (node (ref "PCB1") (pin "49") (pinfunction "49/GND_49") (pintype "bidirectional"))
      (node (ref "PCB1") (pin "50") (pinfunction "50/GND_50") (pintype "bidirectional"))
      (node (ref "PCB1") (pin "55") (pinfunction "55/GND_55") (pintype "bidirectional"))
      (node (ref "PCB1") (pin "56") (pinfunction "56/GND_56") (pintype "bidirectional"))
      (node (ref "PCB1") (pin "61") (pinfunction "61/GND_61") (pintype "bidirectional"))
      (node (ref "PCB1") (pin "62") (pinfunction "62/GND_62") (pintype "bidirectional"))
      (node (ref "PCB1") (pin "67") (pinfunction "67/GND_67") (pintype "bidirectional"))
      (node (ref "PCB1") (pin "68") (pinfunction "68/GND_68") (pintype "bidirectional"))
      (node (ref "PCB1") (pin "7") (pinfunction "7/GND_7") (pintype "bidirectional"))
      (node (ref "PCB1") (pin "73") (pinfunction "73/GND_73") (pintype "bidirectional"))
      (node (ref "PCB1") (pin "74") (pinfunction "74/GND_74") (pintype "bidirectional"))
      (node (ref "PCB1") (pin "79") (pinfunction "79/GND_79") (pintype "bidirectional"))
      (node (ref "PCB1") (pin "80") (pinfunction "80/GND_80") (pintype "bidirectional"))
      (node (ref "PCB1") (pin "85") (pinfunction "85/GND_85") (pintype "bidirectional"))
      (node (ref "PCB1") (pin "86") (pinfunction "86/GND_86") (pintype "bidirectional"))
      (node (ref "PCB1") (pin "91") (pinfunction "91/GND_91") (pintype "bidirectional"))
      (node (ref "PCB1") (pin "92") (pinfunction "92/GND_92") (pintype "bidirectional"))
      (node (ref "PCB1") (pin "97") (pinfunction "97/GND_97") (pintype "bidirectional"))
      (node (ref "PCB1") (pin "98") (pinfunction "98/GND_98") (pintype "bidirectional"))
      (node (ref "R10") (pin "1") (pinfunction "1_1") (pintype "passive"))
      (node (ref "R11") (pin "2") (pinfunction "2_2") (pintype "passive"))
      (node (ref "R12") (pin "2") (pinfunction "2_2") (pintype "passive"))
      (node (ref "R33") (pin "2") (pinfunction "2_2") (pintype "passive"))
      (node (ref "R4") (pin "2") (pinfunction "2_2") (pintype "passive"))
      (node (ref "R5") (pin "2") (pinfunction "2_2") (pintype "passive"))
      (node (ref "U$2") (pin "CON2") (pinfunction "CON02_CON2") (pintype "bidirectional"))
      (node (ref "U1") (pin "1") (pinfunction "CAM_GND_1") (pintype "passive"))
      (node (ref "U1") (pin "10") (pinfunction "CAM_GND_10") (pintype "passive"))
      (node (ref "U1") (pin "4") (pinfunction "CAM_GND_4") (pintype "passive"))
      (node (ref "U1") (pin "7") (pinfunction "CAM_GND_7") (pintype "passive"))
      (node (ref "U2") (pin "1") (pinfunction "CAM_GND_1") (pintype "passive"))
      (node (ref "U2") (pin "10") (pinfunction "CAM_GND_10") (pintype "passive"))
      (node (ref "U2") (pin "4") (pinfunction "CAM_GND_4") (pintype "passive"))
      (node (ref "U2") (pin "7") (pinfunction "CAM_GND_7") (pintype "passive"))
      (node (ref "U3") (pin "2") (pinfunction "S_2") (pintype "passive"))
      (node (ref "U5") (pin "3") (pinfunction "GND_3") (pintype "bidirectional"))
      (node (ref "U5") (pin "9") (pinfunction "GND_9") (pintype "bidirectional"))
      (node (ref "U5") (pin "PAD") (pinfunction "PAD_PAD") (pintype "bidirectional"))
    )
    (net (code "36") (name "GPIO47_1V8") (class "Default")
      (node (ref "PCB1") (pin "90") (pinfunction "90/GPIO47_1V8_90") (pintype "bidirectional"))
      (node (ref "U3") (pin "1") (pinfunction "G_1") (pintype "power_in"))
    )
    (net (code "37") (name "LAN_RUN") (class "Default")
      (node (ref "IC6") (pin "12") (pinfunction "NRESET_12") (pintype "bidirectional"))
      (node (ref "PCB1") (pin "21") (pinfunction "21/GPIO6_21") (pintype "bidirectional"))
    )
    (net (code "38") (name "NLNKA_LED") (class "Default")
      (node (ref "ETHERNET") (pin "10") (pinfunction "P$10_10") (pintype "bidirectional"))
      (node (ref "IC6") (pin "21") (pinfunction "NLNKA_LED/GPIO1_21") (pintype "bidirectional"))
    )
    (net (code "39") (name "NSPD_LED") (class "Default")
      (node (ref "ETHERNET") (pin "11") (pinfunction "P$11_11") (pintype "bidirectional"))
      (node (ref "IC6") (pin "22") (pinfunction "NSPD_LED/GPIO2_22") (pintype "bidirectional"))
    )
    (net (code "40") (name "Net-(C15-Pad+)") (class "Default")
      (node (ref "C15") (pin "+") (pinfunction "+_+") (pintype "passive"))
      (node (ref "F1") (pin "2") (pinfunction "2_2") (pintype "passive"))
      (node (ref "IC1") (pin "IN") (pinfunction "IN_IN") (pintype "input"))
    )
    (net (code "41") (name "Net-(C17-Pad1)") (class "Default")
      (node (ref "C17") (pin "1") (pinfunction "1_1") (pintype "passive"))
      (node (ref "R18") (pin "2") (pinfunction "2_2") (pintype "passive"))
    )
    (net (code "42") (name "Net-(ETHERNET-P$1)") (class "Default")
      (node (ref "C21") (pin "1") (pinfunction "1_1") (pintype "passive"))
      (node (ref "ETHERNET") (pin "1") (pinfunction "P$1_1") (pintype "bidirectional"))
      (node (ref "IC6") (pin "55") (pinfunction "TXP_55") (pintype "bidirectional"))
      (node (ref "R31") (pin "2") (pinfunction "2_2") (pintype "passive"))
    )
    (net (code "43") (name "Net-(ETHERNET-P$2)") (class "Default")
      (node (ref "C22") (pin "1") (pinfunction "1_1") (pintype "passive"))
      (node (ref "ETHERNET") (pin "2") (pinfunction "P$2_2") (pintype "bidirectional"))
      (node (ref "IC6") (pin "56") (pinfunction "TXN_56") (pintype "bidirectional"))
      (node (ref "R30") (pin "2") (pinfunction "2_2") (pintype "passive"))
    )
    (net (code "44") (name "Net-(ETHERNET-P$3)") (class "Default")
      (node (ref "C23") (pin "1") (pinfunction "1_1") (pintype "passive"))
      (node (ref "ETHERNET") (pin "3") (pinfunction "P$3_3") (pintype "bidirectional"))
      (node (ref "IC6") (pin "52") (pinfunction "RXP_52") (pintype "bidirectional"))
      (node (ref "R29") (pin "2") (pinfunction "2_2") (pintype "passive"))
    )
    (net (code "45") (name "Net-(ETHERNET-P$4)") (class "Default")
      (node (ref "C26") (pin "1") (pinfunction "1_1") (pintype "passive"))
      (node (ref "ETHERNET") (pin "4") (pinfunction "P$4_4") (pintype "bidirectional"))
      (node (ref "ETHERNET") (pin "5") (pinfunction "P$5_5") (pintype "bidirectional"))
      (node (ref "R27") (pin "2") (pinfunction "2_2") (pintype "passive"))
    )
    (net (code "46") (name "Net-(ETHERNET-P$6)") (class "Default")
      (node (ref "C24") (pin "1") (pinfunction "1_1") (pintype "passive"))
      (node (ref "ETHERNET") (pin "6") (pinfunction "P$6_6") (pintype "bidirectional"))
      (node (ref "IC6") (pin "53") (pinfunction "RXN_53") (pintype "bidirectional"))
      (node (ref "R28") (pin "2") (pinfunction "2_2") (pintype "passive"))
    )
    (net (code "47") (name "Net-(ETHERNET-P$9)") (class "Default")
      (node (ref "ETHERNET") (pin "9") (pinfunction "P$9_9") (pintype "bidirectional"))
      (node (ref "R26") (pin "2") (pinfunction "2_2") (pintype "passive"))
    )
    (net (code "48") (name "Net-(ETHERNET-P$12)") (class "Default")
      (node (ref "ETHERNET") (pin "12") (pinfunction "P$12_12") (pintype "bidirectional"))
      (node (ref "R25") (pin "2") (pinfunction "2_2") (pintype "passive"))
    )
    (net (code "49") (name "Net-(FB1-Pad2)") (class "Default")
      (node (ref "FB1") (pin "2") (pinfunction "2_2") (pintype "passive"))
      (node (ref "L3") (pin "1") (pinfunction "1_1") (pintype "passive"))
      (node (ref "R18") (pin "1") (pinfunction "1_1") (pintype "passive"))
    )
    (net (code "50") (name "Net-(FB2-P$1)") (class "Default")
      (node (ref "C32") (pin "2") (pinfunction "2_2") (pintype "passive"))
      (node (ref "C33") (pin "2") (pinfunction "2_2") (pintype "passive"))
      (node (ref "C34") (pin "2") (pinfunction "2_2") (pintype "passive"))
      (node (ref "C35") (pin "2") (pinfunction "2_2") (pintype "passive"))
      (node (ref "C36") (pin "2") (pinfunction "2_2") (pintype "passive"))
      (node (ref "C37") (pin "2") (pinfunction "2_2") (pintype "passive"))
      (node (ref "C38") (pin "2") (pinfunction "2_2") (pintype "passive"))
      (node (ref "FB2") (pin "1") (pinfunction "P$1_1") (pintype "bidirectional"))
      (node (ref "IC6") (pin "10") (pinfunction "VDD33A_10") (pintype "bidirectional"))
      (node (ref "IC6") (pin "49") (pinfunction "VDD33A_49") (pintype "bidirectional"))
      (node (ref "IC6") (pin "5") (pinfunction "VDD33A_5") (pintype "bidirectional"))
      (node (ref "IC6") (pin "51") (pinfunction "VDD33A_51") (pintype "bidirectional"))
      (node (ref "IC6") (pin "54") (pinfunction "VDD33A_54") (pintype "bidirectional"))
      (node (ref "IC6") (pin "57") (pinfunction "VDD33A_57") (pintype "bidirectional"))
      (node (ref "IC6") (pin "64") (pinfunction "VDD33A_64") (pintype "bidirectional"))
    )
    (net (code "51") (name "Net-(FB3-P$2)") (class "Default")
      (node (ref "C42") (pin "2") (pinfunction "2_2") (pintype "passive"))
      (node (ref "FB3") (pin "2") (pinfunction "P$2_2") (pintype "bidirectional"))
      (node (ref "IC6") (pin "62") (pinfunction "VDD18USBPLL_62") (pintype "bidirectional"))
    )
    (net (code "52") (name "Net-(IC6-AUTOMDXI_EN)") (class "Default")
      (node (ref "IC6") (pin "41") (pinfunction "AUTOMDXI_EN_41") (pintype "bidirectional"))
      (node (ref "R32") (pin "1") (pinfunction "1_1") (pintype "passive"))
    )
    (net (code "53") (name "Net-(IC6-EXRES)") (class "Default")
      (node (ref "IC6") (pin "50") (pinfunction "EXRES_50") (pintype "bidirectional"))
      (node (ref "R33") (pin "1") (pinfunction "1_1") (pintype "passive"))
    )
    (net (code "54") (name "Net-(IC6-NTRST)") (class "Default")
      (node (ref "IC6") (pin "28") (pinfunction "NTRST_28") (pintype "bidirectional"))
      (node (ref "R20") (pin "1") (pinfunction "1_1") (pintype "passive"))
    )
    (net (code "55") (name "Net-(IC6-USBDM3)") (class "Default")
      (node (ref "IC6") (pin "3") (pinfunction "USBDM3_3") (pintype "bidirectional"))
      (node (ref "K1") (pin "2") (pinfunction "D-_2") (pintype "passive"))
    )
    (net (code "56") (name "Net-(IC6-USBDP3)") (class "Default")
      (node (ref "IC6") (pin "4") (pinfunction "USBDP3_4") (pintype "bidirectional"))
      (node (ref "K1") (pin "3") (pinfunction "D+_3") (pintype "passive"))
    )
    (net (code "57") (name "Net-(IC6-USBRBIAS)") (class "Default")
      (node (ref "IC6") (pin "63") (pinfunction "USBRBIAS_63") (pintype "bidirectional"))
      (node (ref "R10") (pin "2") (pinfunction "2_2") (pintype "passive"))
    )
    (net (code "58") (name "Net-(L1-2)") (class "Default")
      (node (ref "L1") (pin "P$2") (pinfunction "2_P$2") (pintype "passive"))
      (node (ref "U5") (pin "8") (pinfunction "LX1_8") (pintype "bidirectional"))
    )
    (net (code "59") (name "Net-(L2-2)") (class "Default")
      (node (ref "L2") (pin "P$2") (pinfunction "2_P$2") (pintype "passive"))
      (node (ref "U5") (pin "2") (pinfunction "LX2_2") (pintype "bidirectional"))
    )
    (net (code "60") (name "Net-(LED1-PadA)") (class "Default")
      (node (ref "LED1") (pin "A") (pinfunction "A_A") (pintype "passive"))
      (node (ref "R6") (pin "2") (pinfunction "2_2") (pintype "passive"))
    )
    (net (code "61") (name "Net-(LED2-PadA)") (class "Default")
      (node (ref "LED2") (pin "A") (pinfunction "A_A") (pintype "passive"))
      (node (ref "R15") (pin "2") (pinfunction "2_2") (pintype "passive"))
    )
    (net (code "62") (name "Net-(PCB1-82{slash}GPIO44)") (class "Default")
      (node (ref "PCB1") (pin "82") (pinfunction "82/GPIO44_82") (pintype "bidirectional"))
      (node (ref "R12") (pin "1") (pinfunction "1_1") (pintype "passive"))
    )
    (net (code "63") (name "Net-(PCB1-84{slash}GPIO45)") (class "Default")
      (node (ref "PCB1") (pin "84") (pinfunction "84/GPIO45_84") (pintype "bidirectional"))
      (node (ref "R11") (pin "1") (pinfunction "1_1") (pintype "passive"))
    )
    (net (code "64") (name "Net-(U3-D)") (class "Default")
      (node (ref "LED2") (pin "C") (pinfunction "C_C") (pintype "passive"))
      (node (ref "U3") (pin "3") (pinfunction "D_3") (pintype "output"))
    )
    (net (code "65") (name "Net-(U5-EN2)") (class "Default")
      (node (ref "C1") (pin "1") (pinfunction "1_1") (pintype "passive"))
      (node (ref "R1") (pin "2") (pinfunction "2_2") (pintype "passive"))
      (node (ref "U5") (pin "12") (pinfunction "EN2_12") (pintype "bidirectional"))
    )
    (net (code "66") (name "Net-(U5-FB1)") (class "Default")
      (node (ref "C4") (pin "2") (pinfunction "2_2") (pintype "passive"))
      (node (ref "R2") (pin "2") (pinfunction "2_2") (pintype "passive"))
      (node (ref "R5") (pin "1") (pinfunction "1_1") (pintype "passive"))
      (node (ref "U5") (pin "4") (pinfunction "FB1_4") (pintype "bidirectional"))
    )
    (net (code "67") (name "Net-(U5-FB2)") (class "Default")
      (node (ref "C5") (pin "2") (pinfunction "2_2") (pintype "passive"))
      (node (ref "R3") (pin "2") (pinfunction "2_2") (pintype "passive"))
      (node (ref "R4") (pin "1") (pinfunction "1_1") (pintype "passive"))
      (node (ref "U5") (pin "10") (pinfunction "FB2_10") (pintype "bidirectional"))
    )
    (net (code "68") (name "TOP_LIGHT_ENABLED") (class "Default")
      (node (ref "PCB1") (pin "57") (pinfunction "57/GPIO16_57") (pintype "bidirectional"))
    )
    (net (code "69") (name "UART0_RX") (class "Default")
      (node (ref "JP1") (pin "5") (pinfunction "5_5") (pintype "passive"))
      (node (ref "PCB1") (pin "53") (pinfunction "53/GPIO15_53") (pintype "bidirectional"))
    )
    (net (code "70") (name "UART0_TX") (class "Default")
      (node (ref "JP1") (pin "3") (pinfunction "3_3") (pintype "passive"))
      (node (ref "PCB1") (pin "51") (pinfunction "51/GPIO14_51") (pintype "bidirectional"))
    )
    (net (code "71") (name "USB_D_N") (class "Default")
      (node (ref "IC6") (pin "58") (pinfunction "USBDM0_58") (pintype "bidirectional"))
      (node (ref "PCB1") (pin "167") (pinfunction "167/USB_DM**_167") (pintype "bidirectional"))
    )
    (net (code "72") (name "USB_D_P") (class "Default")
      (node (ref "IC6") (pin "59") (pinfunction "USBDP0_59") (pintype "bidirectional"))
      (node (ref "PCB1") (pin "165") (pinfunction "165/USB_DP**_165") (pintype "bidirectional"))
    )
    (net (code "73") (name "VDD18CORE") (class "Default")
      (node (ref "C39") (pin "2") (pinfunction "2_2") (pintype "passive"))
      (node (ref "C40") (pin "2") (pinfunction "2_2") (pintype "passive"))
      (node (ref "C41") (pin "2") (pinfunction "2_2") (pintype "passive"))
      (node (ref "IC6") (pin "15") (pinfunction "VDD18CORE_15") (pintype "bidirectional"))
      (node (ref "IC6") (pin "38") (pinfunction "VDD18CORE_38") (pintype "bidirectional"))
    )
    (net (code "74") (name "VDD18PLL") (class "Default")
      (node (ref "C43") (pin "2") (pinfunction "2_2") (pintype "passive"))
      (node (ref "FB3") (pin "1") (pinfunction "P$1_1") (pintype "bidirectional"))
      (node (ref "IC6") (pin "48") (pinfunction "VDD18ETHPLL_48") (pintype "bidirectional"))
    )
    (net (code "75") (name "XI") (class "Default")
      (node (ref "C45") (pin "2") (pinfunction "2_2") (pintype "passive"))
      (node (ref "IC6") (pin "61") (pinfunction "XI_61") (pintype "bidirectional"))
      (node (ref "Q6") (pin "1") (pinfunction "X1_1") (pintype "bidirectional"))
      (node (ref "R19") (pin "2") (pinfunction "2_2") (pintype "passive"))
    )
    (net (code "76") (name "XO") (class "Default")
      (node (ref "C44") (pin "2") (pinfunction "2_2") (pintype "passive"))
      (node (ref "IC6") (pin "60") (pinfunction "XO_60") (pintype "bidirectional"))
      (node (ref "Q6") (pin "3") (pinfunction "X2_3") (pintype "bidirectional"))
      (node (ref "R19") (pin "1") (pinfunction "1_1") (pintype "passive"))
    )
    (net (code "77") (name "unconnected-(ETHERNET-P$7-Pad7)") (class "Default")
      (node (ref "ETHERNET") (pin "7") (pinfunction "P$7_7") (pintype "bidirectional"))
    )
    (net (code "78") (name "unconnected-(IC6-CLK24_OUT-Pad45)") (class "Default")
      (node (ref "IC6") (pin "45") (pinfunction "CLK24_OUT_45") (pintype "bidirectional"))
    )
    (net (code "79") (name "unconnected-(IC6-EECLK-Pad23)") (class "Default")
      (node (ref "IC6") (pin "23") (pinfunction "EECLK_23") (pintype "bidirectional"))
    )
    (net (code "80") (name "unconnected-(IC6-EECS-Pad24)") (class "Default")
      (node (ref "IC6") (pin "24") (pinfunction "EECS_24") (pintype "bidirectional"))
    )
    (net (code "81") (name "unconnected-(IC6-EEDI-Pad26)") (class "Default")
      (node (ref "IC6") (pin "26") (pinfunction "EEDI_26") (pintype "bidirectional"))
    )
    (net (code "82") (name "unconnected-(IC6-EEDO-Pad25)") (class "Default")
      (node (ref "IC6") (pin "25") (pinfunction "EEDO_25") (pintype "bidirectional"))
    )
    (net (code "83") (name "unconnected-(IC6-GPIO3-Pad35)") (class "Default")
      (node (ref "IC6") (pin "35") (pinfunction "GPIO3_35") (pintype "bidirectional"))
    )
    (net (code "84") (name "unconnected-(IC6-GPIO4-Pad36)") (class "Default")
      (node (ref "IC6") (pin "36") (pinfunction "GPIO4_36") (pintype "bidirectional"))
    )
    (net (code "85") (name "unconnected-(IC6-GPIO5-Pad37)") (class "Default")
      (node (ref "IC6") (pin "37") (pinfunction "GPIO5_37") (pintype "bidirectional"))
    )
    (net (code "86") (name "unconnected-(IC6-GPIO6-Pad42)") (class "Default")
      (node (ref "IC6") (pin "42") (pinfunction "GPIO6_42") (pintype "bidirectional"))
    )
    (net (code "87") (name "unconnected-(IC6-GPIO7-Pad43)") (class "Default")
      (node (ref "IC6") (pin "43") (pinfunction "GPIO7_43") (pintype "bidirectional"))
    )
    (net (code "88") (name "unconnected-(IC6-NC-Pad6)") (class "Default")
      (node (ref "IC6") (pin "6") (pinfunction "NC_6") (pintype "bidirectional"))
    )
    (net (code "89") (name "unconnected-(IC6-NC-Pad7)") (class "Default")
      (node (ref "IC6") (pin "7") (pinfunction "NC_7") (pintype "bidirectional"))
    )
    (net (code "90") (name "unconnected-(IC6-NC-Pad8)") (class "Default")
      (node (ref "IC6") (pin "8") (pinfunction "NC_8") (pintype "bidirectional"))
    )
    (net (code "91") (name "unconnected-(IC6-NC-Pad9)") (class "Default")
      (node (ref "IC6") (pin "9") (pinfunction "NC_9") (pintype "bidirectional"))
    )
    (net (code "92") (name "unconnected-(IC6-NC-Pad17)") (class "Default")
      (node (ref "IC6") (pin "17") (pinfunction "NC_17") (pintype "bidirectional"))
    )
    (net (code "93") (name "unconnected-(IC6-NC-Pad18)") (class "Default")
      (node (ref "IC6") (pin "18") (pinfunction "NC_18") (pintype "bidirectional"))
    )
    (net (code "94") (name "unconnected-(IC6-NFDX_LED{slash}GPIO0-Pad20)") (class "Default")
      (node (ref "IC6") (pin "20") (pinfunction "NFDX_LED/GPIO0_20") (pintype "bidirectional"))
    )
    (net (code "95") (name "unconnected-(IC6-PRTCTL2-Pad14)") (class "Default")
      (node (ref "IC6") (pin "14") (pinfunction "PRTCTL2_14") (pintype "bidirectional"))
    )
    (net (code "96") (name "unconnected-(IC6-PRTCTL3-Pad16)") (class "Default")
      (node (ref "IC6") (pin "16") (pinfunction "PRTCTL3_16") (pintype "bidirectional"))
    )
    (net (code "97") (name "unconnected-(IC6-TCK-Pad32)") (class "Default")
      (node (ref "IC6") (pin "32") (pinfunction "TCK_32") (pintype "bidirectional"))
    )
    (net (code "98") (name "unconnected-(IC6-TDI-Pad30)") (class "Default")
      (node (ref "IC6") (pin "30") (pinfunction "TDI_30") (pintype "bidirectional"))
    )
    (net (code "99") (name "unconnected-(IC6-TDO-Pad31)") (class "Default")
      (node (ref "IC6") (pin "31") (pinfunction "TDO_31") (pintype "bidirectional"))
    )
    (net (code "100") (name "unconnected-(IC6-TEST1-Pad13)") (class "Default")
      (node (ref "IC6") (pin "13") (pinfunction "TEST1_13") (pintype "bidirectional"))
    )
    (net (code "101") (name "unconnected-(IC6-TEST4-Pad47)") (class "Default")
      (node (ref "IC6") (pin "47") (pinfunction "TEST4_47") (pintype "bidirectional"))
    )
    (net (code "102") (name "unconnected-(IC6-TMS-Pad29)") (class "Default")
      (node (ref "IC6") (pin "29") (pinfunction "TMS_29") (pintype "bidirectional"))
    )
    (net (code "103") (name "unconnected-(IC6-USBDM2-Pad1)") (class "Default")
      (node (ref "IC6") (pin "1") (pinfunction "USBDM2_1") (pintype "bidirectional"))
    )
    (net (code "104") (name "unconnected-(IC6-USBDP2-Pad2)") (class "Default")
      (node (ref "IC6") (pin "2") (pinfunction "USBDP2_2") (pintype "bidirectional"))
    )
    (net (code "105") (name "unconnected-(JP2-Pad3)") (class "Default")
      (node (ref "JP2") (pin "3") (pinfunction "3_3") (pintype "passive"))
    )
    (net (code "106") (name "unconnected-(JP2-Pad4)") (class "Default")
      (node (ref "JP2") (pin "4") (pinfunction "4_4") (pintype "passive"))
    )
    (net (code "107") (name "unconnected-(JP3-Pad2)") (class "Default")
      (node (ref "JP3") (pin "2") (pinfunction "2_2") (pintype "passive"))
    )
    (net (code "108") (name "unconnected-(JP3-Pad3)") (class "Default")
      (node (ref "JP3") (pin "3") (pinfunction "3_3") (pintype "passive"))
    )
    (net (code "109") (name "unconnected-(JP3-Pad4)") (class "Default")
      (node (ref "JP3") (pin "4") (pinfunction "4_4") (pintype "passive"))
    )
    (net (code "110") (name "unconnected-(PCB1-4{slash}NC-Pad4)") (class "Default")
      (node (ref "PCB1") (pin "4") (pinfunction "4/NC_4") (pintype "bidirectional"))
    )
    (net (code "111") (name "unconnected-(PCB1-6{slash}NC-Pad6)") (class "Default")
      (node (ref "PCB1") (pin "6") (pinfunction "6/NC_6") (pintype "bidirectional"))
    )
    (net (code "112") (name "unconnected-(PCB1-8{slash}NC-Pad8)") (class "Default")
      (node (ref "PCB1") (pin "8") (pinfunction "8/NC_8") (pintype "bidirectional"))
    )
    (net (code "113") (name "unconnected-(PCB1-10{slash}NC-Pad10)") (class "Default")
      (node (ref "PCB1") (pin "10") (pinfunction "10/NC_10") (pintype "bidirectional"))
    )
    (net (code "114") (name "unconnected-(PCB1-12{slash}NC-Pad12)") (class "Default")
      (node (ref "PCB1") (pin "12") (pinfunction "12/NC_12") (pintype "bidirectional"))
    )
    (net (code "115") (name "unconnected-(PCB1-14{slash}NC-Pad14)") (class "Default")
      (node (ref "PCB1") (pin "14") (pinfunction "14/NC_14") (pintype "bidirectional"))
    )
    (net (code "116") (name "unconnected-(PCB1-15{slash}GPIO4-Pad15)") (class "Default")
      (node (ref "PCB1") (pin "15") (pinfunction "15/GPIO4_15") (pintype "bidirectional"))
    )
    (net (code "117") (name "unconnected-(PCB1-16{slash}NC-Pad16)") (class "Default")
      (node (ref "PCB1") (pin "16") (pinfunction "16/NC_16") (pintype "bidirectional"))
    )
    (net (code "118") (name "unconnected-(PCB1-17{slash}GPIO5-Pad17)") (class "Default")
      (node (ref "PCB1") (pin "17") (pinfunction "17/GPIO5_17") (pintype "bidirectional"))
    )
    (net (code "119") (name "unconnected-(PCB1-18{slash}NC-Pad18)") (class "Default")
      (node (ref "PCB1") (pin "18") (pinfunction "18/NC_18") (pintype "bidirectional"))
    )
    (net (code "120") (name "unconnected-(PCB1-20{slash}NC-Pad20)") (class "Default")
      (node (ref "PCB1") (pin "20") (pinfunction "20/NC_20") (pintype "bidirectional"))
    )
    (net (code "121") (name "unconnected-(PCB1-22{slash}NC-Pad22)") (class "Default")
      (node (ref "PCB1") (pin "22") (pinfunction "22/NC_22") (pintype "bidirectional"))
    )
    (net (code "122") (name "unconnected-(PCB1-23{slash}GPIO7-Pad23)") (class "Default")
      (node (ref "PCB1") (pin "23") (pinfunction "23/GPIO7_23") (pintype "bidirectional"))
    )
    (net (code "123") (name "unconnected-(PCB1-24{slash}NC-Pad24)") (class "Default")
      (node (ref "PCB1") (pin "24") (pinfunction "24/NC_24") (pintype "bidirectional"))
    )
    (net (code "124") (name "unconnected-(PCB1-27{slash}GPIO8-Pad27)") (class "Default")
      (node (ref "PCB1") (pin "27") (pinfunction "27/GPIO8_27") (pintype "bidirectional"))
    )
    (net (code "125") (name "unconnected-(PCB1-29{slash}GPIO9-Pad29)") (class "Default")
      (node (ref "PCB1") (pin "29") (pinfunction "29/GPIO9_29") (pintype "bidirectional"))
    )
    (net (code "126") (name "unconnected-(PCB1-33{slash}GPIO10-Pad33)") (class "Default")
      (node (ref "PCB1") (pin "33") (pinfunction "33/GPIO10_33") (pintype "bidirectional"))
    )
    (net (code "127") (name "unconnected-(PCB1-35{slash}GPIO11-Pad35)") (class "Default")
      (node (ref "PCB1") (pin "35") (pinfunction "35/GPIO11_35") (pintype "bidirectional"))
    )
    (net (code "128") (name "unconnected-(PCB1-45{slash}GPIO12-Pad45)") (class "Default")
      (node (ref "PCB1") (pin "45") (pinfunction "45/GPIO12_45") (pintype "bidirectional"))
    )
    (net (code "129") (name "unconnected-(PCB1-46{slash}GPIO32-Pad46)") (class "Default")
      (node (ref "PCB1") (pin "46") (pinfunction "46/GPIO32_46") (pintype "bidirectional"))
    )
    (net (code "130") (name "unconnected-(PCB1-47{slash}GPIO13-Pad47)") (class "Default")
      (node (ref "PCB1") (pin "47") (pinfunction "47/GPIO13_47") (pintype "bidirectional"))
    )
    (net (code "131") (name "unconnected-(PCB1-48{slash}GPIO33-Pad48)") (class "Default")
      (node (ref "PCB1") (pin "48") (pinfunction "48/GPIO33_48") (pintype "bidirectional"))
    )
    (net (code "132") (name "unconnected-(PCB1-52{slash}GPIO34-Pad52)") (class "Default")
      (node (ref "PCB1") (pin "52") (pinfunction "52/GPIO34_52") (pintype "bidirectional"))
    )
    (net (code "133") (name "unconnected-(PCB1-54{slash}GPIO35-Pad54)") (class "Default")
      (node (ref "PCB1") (pin "54") (pinfunction "54/GPIO35_54") (pintype "bidirectional"))
    )
    (net (code "134") (name "unconnected-(PCB1-58{slash}GPIO36-Pad58)") (class "Default")
      (node (ref "PCB1") (pin "58") (pinfunction "58/GPIO36_58") (pintype "bidirectional"))
    )
    (net (code "135") (name "unconnected-(PCB1-60{slash}GPIO37-Pad60)") (class "Default")
      (node (ref "PCB1") (pin "60") (pinfunction "60/GPIO37_60") (pintype "bidirectional"))
    )
    (net (code "136") (name "unconnected-(PCB1-63{slash}GPIO18-Pad63)") (class "Default")
      (node (ref "PCB1") (pin "63") (pinfunction "63/GPIO18_63") (pintype "bidirectional"))
    )
    (net (code "137") (name "unconnected-(PCB1-64{slash}GPIO38-Pad64)") (class "Default")
      (node (ref "PCB1") (pin "64") (pinfunction "64/GPIO38_64") (pintype "bidirectional"))
    )
    (net (code "138") (name "unconnected-(PCB1-65{slash}GPIO19-Pad65)") (class "Default")
      (node (ref "PCB1") (pin "65") (pinfunction "65/GPIO19_65") (pintype "bidirectional"))
    )
    (net (code "139") (name "unconnected-(PCB1-66{slash}GPIO39-Pad66)") (class "Default")
      (node (ref "PCB1") (pin "66") (pinfunction "66/GPIO39_66") (pintype "bidirectional"))
    )
    (net (code "140") (name "unconnected-(PCB1-69{slash}GPIO20-Pad69)") (class "Default")
      (node (ref "PCB1") (pin "69") (pinfunction "69/GPIO20_69") (pintype "bidirectional"))
    )
    (net (code "141") (name "unconnected-(PCB1-71{slash}GPIO21-Pad71)") (class "Default")
      (node (ref "PCB1") (pin "71") (pinfunction "71/GPIO21_71") (pintype "bidirectional"))
    )
    (net (code "142") (name "unconnected-(PCB1-75{slash}GPIO22-Pad75)") (class "Default")
      (node (ref "PCB1") (pin "75") (pinfunction "75/GPIO22_75") (pintype "bidirectional"))
    )
    (net (code "143") (name "unconnected-(PCB1-76{slash}GPIO42-Pad76)") (class "Default")
      (node (ref "PCB1") (pin "76") (pinfunction "76/GPIO42_76") (pintype "bidirectional"))
    )
    (net (code "144") (name "unconnected-(PCB1-77{slash}GPIO23-Pad77)") (class "Default")
      (node (ref "PCB1") (pin "77") (pinfunction "77/GPIO23_77") (pintype "bidirectional"))
    )
    (net (code "145") (name "unconnected-(PCB1-78{slash}GPIO43-Pad78)") (class "Default")
      (node (ref "PCB1") (pin "78") (pinfunction "78/GPIO43_78") (pintype "bidirectional"))
    )
    (net (code "146") (name "unconnected-(PCB1-81{slash}GPIO24-Pad81)") (class "Default")
      (node (ref "PCB1") (pin "81") (pinfunction "81/GPIO24_81") (pintype "bidirectional"))
    )
    (net (code "147") (name "unconnected-(PCB1-83{slash}GPIO25-Pad83)") (class "Default")
      (node (ref "PCB1") (pin "83") (pinfunction "83/GPIO25_83") (pintype "bidirectional"))
    )
    (net (code "148") (name "unconnected-(PCB1-87{slash}GPIO26-Pad87)") (class "Default")
      (node (ref "PCB1") (pin "87") (pinfunction "87/GPIO26_87") (pintype "bidirectional"))
    )
    (net (code "149") (name "unconnected-(PCB1-88{slash}GPIO46_1V8-Pad88)") (class "Default")
      (node (ref "PCB1") (pin "88") (pinfunction "88/GPIO46_1V8_88") (pintype "bidirectional"))
    )
    (net (code "150") (name "unconnected-(PCB1-89{slash}GPIO27-Pad89)") (class "Default")
      (node (ref "PCB1") (pin "89") (pinfunction "89/GPIO27_89") (pintype "bidirectional"))
    )
    (net (code "151") (name "unconnected-(PCB1-93{slash}DSI0_DN1*-Pad93)") (class "Default")
      (node (ref "PCB1") (pin "93") (pinfunction "93/DSI0_DN1*_93") (pintype "bidirectional"))
    )
    (net (code "152") (name "unconnected-(PCB1-94{slash}DSI1_DP0*-Pad94)") (class "Default")
      (node (ref "PCB1") (pin "94") (pinfunction "94/DSI1_DP0*_94") (pintype "bidirectional"))
    )
    (net (code "153") (name "unconnected-(PCB1-95{slash}DSI0_DP1*-Pad95)") (class "Default")
      (node (ref "PCB1") (pin "95") (pinfunction "95/DSI0_DP1*_95") (pintype "bidirectional"))
    )
    (net (code "154") (name "unconnected-(PCB1-96{slash}DSI1_DN0*-Pad96)") (class "Default")
      (node (ref "PCB1") (pin "96") (pinfunction "96/DSI1_DN0*_96") (pintype "bidirectional"))
    )
    (net (code "155") (name "unconnected-(PCB1-99{slash}DSI0_DN0*-Pad99)") (class "Default")
      (node (ref "PCB1") (pin "99") (pinfunction "99/DSI0_DN0*_99") (pintype "bidirectional"))
    )
    (net (code "156") (name "unconnected-(PCB1-100{slash}DSI1CP*-Pad100)") (class "Default")
      (node (ref "PCB1") (pin "100") (pinfunction "100/DSI1CP*_100") (pintype "bidirectional"))
    )
    (net (code "157") (name "unconnected-(PCB1-101{slash}DSI0_DP0*-Pad101)") (class "Default")
      (node (ref "PCB1") (pin "101") (pinfunction "101/DSI0_DP0*_101") (pintype "bidirectional"))
    )
    (net (code "158") (name "unconnected-(PCB1-102{slash}DSI1CN*-Pad102)") (class "Default")
      (node (ref "PCB1") (pin "102") (pinfunction "102/DSI1CN*_102") (pintype "bidirectional"))
    )
    (net (code "159") (name "unconnected-(PCB1-105{slash}DSI0_CN*-Pad105)") (class "Default")
      (node (ref "PCB1") (pin "105") (pinfunction "105/DSI0_CN*_105") (pintype "bidirectional"))
    )
    (net (code "160") (name "unconnected-(PCB1-106{slash}DSI1_DP3*-Pad106)") (class "Default")
      (node (ref "PCB1") (pin "106") (pinfunction "106/DSI1_DP3*_106") (pintype "bidirectional"))
    )
    (net (code "161") (name "unconnected-(PCB1-107{slash}DSI0_CP*-Pad107)") (class "Default")
      (node (ref "PCB1") (pin "107") (pinfunction "107/DSI0_CP*_107") (pintype "bidirectional"))
    )
    (net (code "162") (name "unconnected-(PCB1-108{slash}DSI1_DN3*-Pad108)") (class "Default")
      (node (ref "PCB1") (pin "108") (pinfunction "108/DSI1_DN3*_108") (pintype "bidirectional"))
    )
    (net (code "163") (name "unconnected-(PCB1-111{slash}HDMI_CK_N*-Pad111)") (class "Default")
      (node (ref "PCB1") (pin "111") (pinfunction "111/HDMI_CK_N*_111") (pintype "bidirectional"))
    )
    (net (code "164") (name "unconnected-(PCB1-112{slash}DSI1_DP2*-Pad112)") (class "Default")
      (node (ref "PCB1") (pin "112") (pinfunction "112/DSI1_DP2*_112") (pintype "bidirectional"))
    )
    (net (code "165") (name "unconnected-(PCB1-113{slash}HDMI_CK_P*-Pad113)") (class "Default")
      (node (ref "PCB1") (pin "113") (pinfunction "113/HDMI_CK_P*_113") (pintype "bidirectional"))
    )
    (net (code "166") (name "unconnected-(PCB1-114{slash}DSI1_DN2*-Pad114)") (class "Default")
      (node (ref "PCB1") (pin "114") (pinfunction "114/DSI1_DN2*_114") (pintype "bidirectional"))
    )
    (net (code "167") (name "unconnected-(PCB1-116{slash}GND-Pad116)") (class "Default")
      (node (ref "PCB1") (pin "116") (pinfunction "116/GND_116") (pintype "bidirectional"))
    )
    (net (code "168") (name "unconnected-(PCB1-117{slash}HDMI_D0_N*-Pad117)") (class "Default")
      (node (ref "PCB1") (pin "117") (pinfunction "117/HDMI_D0_N*_117") (pintype "bidirectional"))
    )
    (net (code "169") (name "unconnected-(PCB1-118{slash}DSI1_DP1*-Pad118)") (class "Default")
      (node (ref "PCB1") (pin "118") (pinfunction "118/DSI1_DP1*_118") (pintype "bidirectional"))
    )
    (net (code "170") (name "unconnected-(PCB1-119{slash}HDMI_D0_P*-Pad119)") (class "Default")
      (node (ref "PCB1") (pin "119") (pinfunction "119/HDMI_D0_P*_119") (pintype "bidirectional"))
    )
    (net (code "171") (name "unconnected-(PCB1-120{slash}DSI1_DN1*-Pad120)") (class "Default")
      (node (ref "PCB1") (pin "120") (pinfunction "120/DSI1_DN1*_120") (pintype "bidirectional"))
    )
    (net (code "172") (name "unconnected-(PCB1-123{slash}HDMI_D1_N*-Pad123)") (class "Default")
      (node (ref "PCB1") (pin "123") (pinfunction "123/HDMI_D1_N*_123") (pintype "bidirectional"))
    )
    (net (code "173") (name "unconnected-(PCB1-124{slash}NC-Pad124)") (class "Default")
      (node (ref "PCB1") (pin "124") (pinfunction "124/NC_124") (pintype "bidirectional"))
    )
    (net (code "174") (name "unconnected-(PCB1-125{slash}HDMI_D1_P*-Pad125)") (class "Default")
      (node (ref "PCB1") (pin "125") (pinfunction "125/HDMI_D1_P*_125") (pintype "bidirectional"))
    )
    (net (code "175") (name "unconnected-(PCB1-126{slash}NC-Pad126)") (class "Default")
      (node (ref "PCB1") (pin "126") (pinfunction "126/NC_126") (pintype "bidirectional"))
    )
    (net (code "176") (name "unconnected-(PCB1-128{slash}NC-Pad128)") (class "Default")
      (node (ref "PCB1") (pin "128") (pinfunction "128/NC_128") (pintype "bidirectional"))
    )
    (net (code "177") (name "unconnected-(PCB1-129{slash}HDMI_D2_N*-Pad129)") (class "Default")
      (node (ref "PCB1") (pin "129") (pinfunction "129/HDMI_D2_N*_129") (pintype "bidirectional"))
    )
    (net (code "178") (name "unconnected-(PCB1-130{slash}NC-Pad130)") (class "Default")
      (node (ref "PCB1") (pin "130") (pinfunction "130/NC_130") (pintype "bidirectional"))
    )
    (net (code "179") (name "unconnected-(PCB1-131{slash}HDMI_D2_P*-Pad131)") (class "Default")
      (node (ref "PCB1") (pin "131") (pinfunction "131/HDMI_D2_P*_131") (pintype "bidirectional"))
    )
    (net (code "180") (name "unconnected-(PCB1-132{slash}NC-Pad132)") (class "Default")
      (node (ref "PCB1") (pin "132") (pinfunction "132/NC_132") (pintype "bidirectional"))
    )
    (net (code "181") (name "unconnected-(PCB1-135{slash}CAM1_DP3*-Pad135)") (class "Default")
      (node (ref "PCB1") (pin "135") (pinfunction "135/CAM1_DP3*_135") (pintype "bidirectional"))
    )
    (net (code "182") (name "unconnected-(PCB1-137{slash}CAM1_DN3*-Pad137)") (class "Default")
      (node (ref "PCB1") (pin "137") (pinfunction "137/CAM1_DN3*_137") (pintype "bidirectional"))
    )
    (net (code "183") (name "unconnected-(PCB1-141{slash}CAM1_DP2*-Pad141)") (class "Default")
      (node (ref "PCB1") (pin "141") (pinfunction "141/CAM1_DP2*_141") (pintype "bidirectional"))
    )
    (net (code "184") (name "unconnected-(PCB1-143{slash}CAM1_DN2*-Pad143)") (class "Default")
      (node (ref "PCB1") (pin "143") (pinfunction "143/CAM1_DN2*_143") (pintype "bidirectional"))
    )
    (net (code "185") (name "unconnected-(PCB1-154{slash}NC-Pad154)") (class "Default")
      (node (ref "PCB1") (pin "154") (pinfunction "154/NC_154") (pintype "bidirectional"))
    )
    (net (code "186") (name "unconnected-(PCB1-156{slash}NC-Pad156)") (class "Default")
      (node (ref "PCB1") (pin "156") (pinfunction "156/NC_156") (pintype "bidirectional"))
    )
    (net (code "187") (name "unconnected-(PCB1-158{slash}NC-Pad158)") (class "Default")
      (node (ref "PCB1") (pin "158") (pinfunction "158/NC_158") (pintype "bidirectional"))
    )
    (net (code "188") (name "unconnected-(PCB1-160{slash}NC-Pad160)") (class "Default")
      (node (ref "PCB1") (pin "160") (pinfunction "160/NC_160") (pintype "bidirectional"))
    )
    (net (code "189") (name "unconnected-(PCB1-162{slash}NC-Pad162)") (class "Default")
      (node (ref "PCB1") (pin "162") (pinfunction "162/NC_162") (pintype "bidirectional"))
    )
    (net (code "190") (name "unconnected-(PCB1-166{slash}TVDAC-Pad166)") (class "Default")
      (node (ref "PCB1") (pin "166") (pinfunction "166/TVDAC_166") (pintype "bidirectional"))
    )
    (net (code "191") (name "unconnected-(PCB1-171{slash}HDMI_CEC-Pad171)") (class "Default")
      (node (ref "PCB1") (pin "171") (pinfunction "171/HDMI_CEC_171") (pintype "bidirectional"))
    )
    (net (code "192") (name "unconnected-(PCB1-172{slash}VC_TRST_N-Pad172)") (class "Default")
      (node (ref "PCB1") (pin "172") (pinfunction "172/VC_TRST_N_172") (pintype "bidirectional"))
    )
    (net (code "193") (name "unconnected-(PCB1-173{slash}HDMI_SDA-Pad173)") (class "Default")
      (node (ref "PCB1") (pin "173") (pinfunction "173/HDMI_SDA_173") (pintype "bidirectional"))
    )
    (net (code "194") (name "unconnected-(PCB1-174{slash}VC_TDI-Pad174)") (class "Default")
      (node (ref "PCB1") (pin "174") (pinfunction "174/VC_TDI_174") (pintype "bidirectional"))
    )
    (net (code "195") (name "unconnected-(PCB1-175{slash}HDMI_SCL-Pad175)") (class "Default")
      (node (ref "PCB1") (pin "175") (pinfunction "175/HDMI_SCL_175") (pintype "bidirectional"))
    )
    (net (code "196") (name "unconnected-(PCB1-176{slash}VC_TMS-Pad176)") (class "Default")
      (node (ref "PCB1") (pin "176") (pinfunction "176/VC_TMS_176") (pintype "bidirectional"))
    )
    (net (code "197") (name "unconnected-(PCB1-177{slash}RUN-Pad177)") (class "Default")
      (node (ref "PCB1") (pin "177") (pinfunction "177/RUN_177") (pintype "bidirectional"))
    )
    (net (code "198") (name "unconnected-(PCB1-178{slash}VC_TDO-Pad178)") (class "Default")
      (node (ref "PCB1") (pin "178") (pinfunction "178/VC_TDO_178") (pintype "bidirectional"))
    )
    (net (code "199") (name "unconnected-(PCB1-179{slash}VDD_CORE-Pad179)") (class "Default")
      (node (ref "PCB1") (pin "179") (pinfunction "179/VDD_CORE_179") (pintype "bidirectional"))
    )
    (net (code "200") (name "unconnected-(PCB1-180{slash}VC_TCK-Pad180)") (class "Default")
      (node (ref "PCB1") (pin "180") (pinfunction "180/VC_TCK_180") (pintype "bidirectional"))
    )
    (net (code "201") (name "unconnected-(U5-NC1-Pad5)") (class "Default")
      (node (ref "U5") (pin "5") (pinfunction "NC1_5") (pintype "bidirectional"))
    )
    (net (code "202") (name "unconnected-(U5-NC2-Pad11)") (class "Default")
      (node (ref "U5") (pin "11") (pinfunction "NC2_11") (pintype "bidirectional"))
    )
  )
)
